# hackeeg-shield.net
KiCad netlist of a schematic drawn in EAGLE
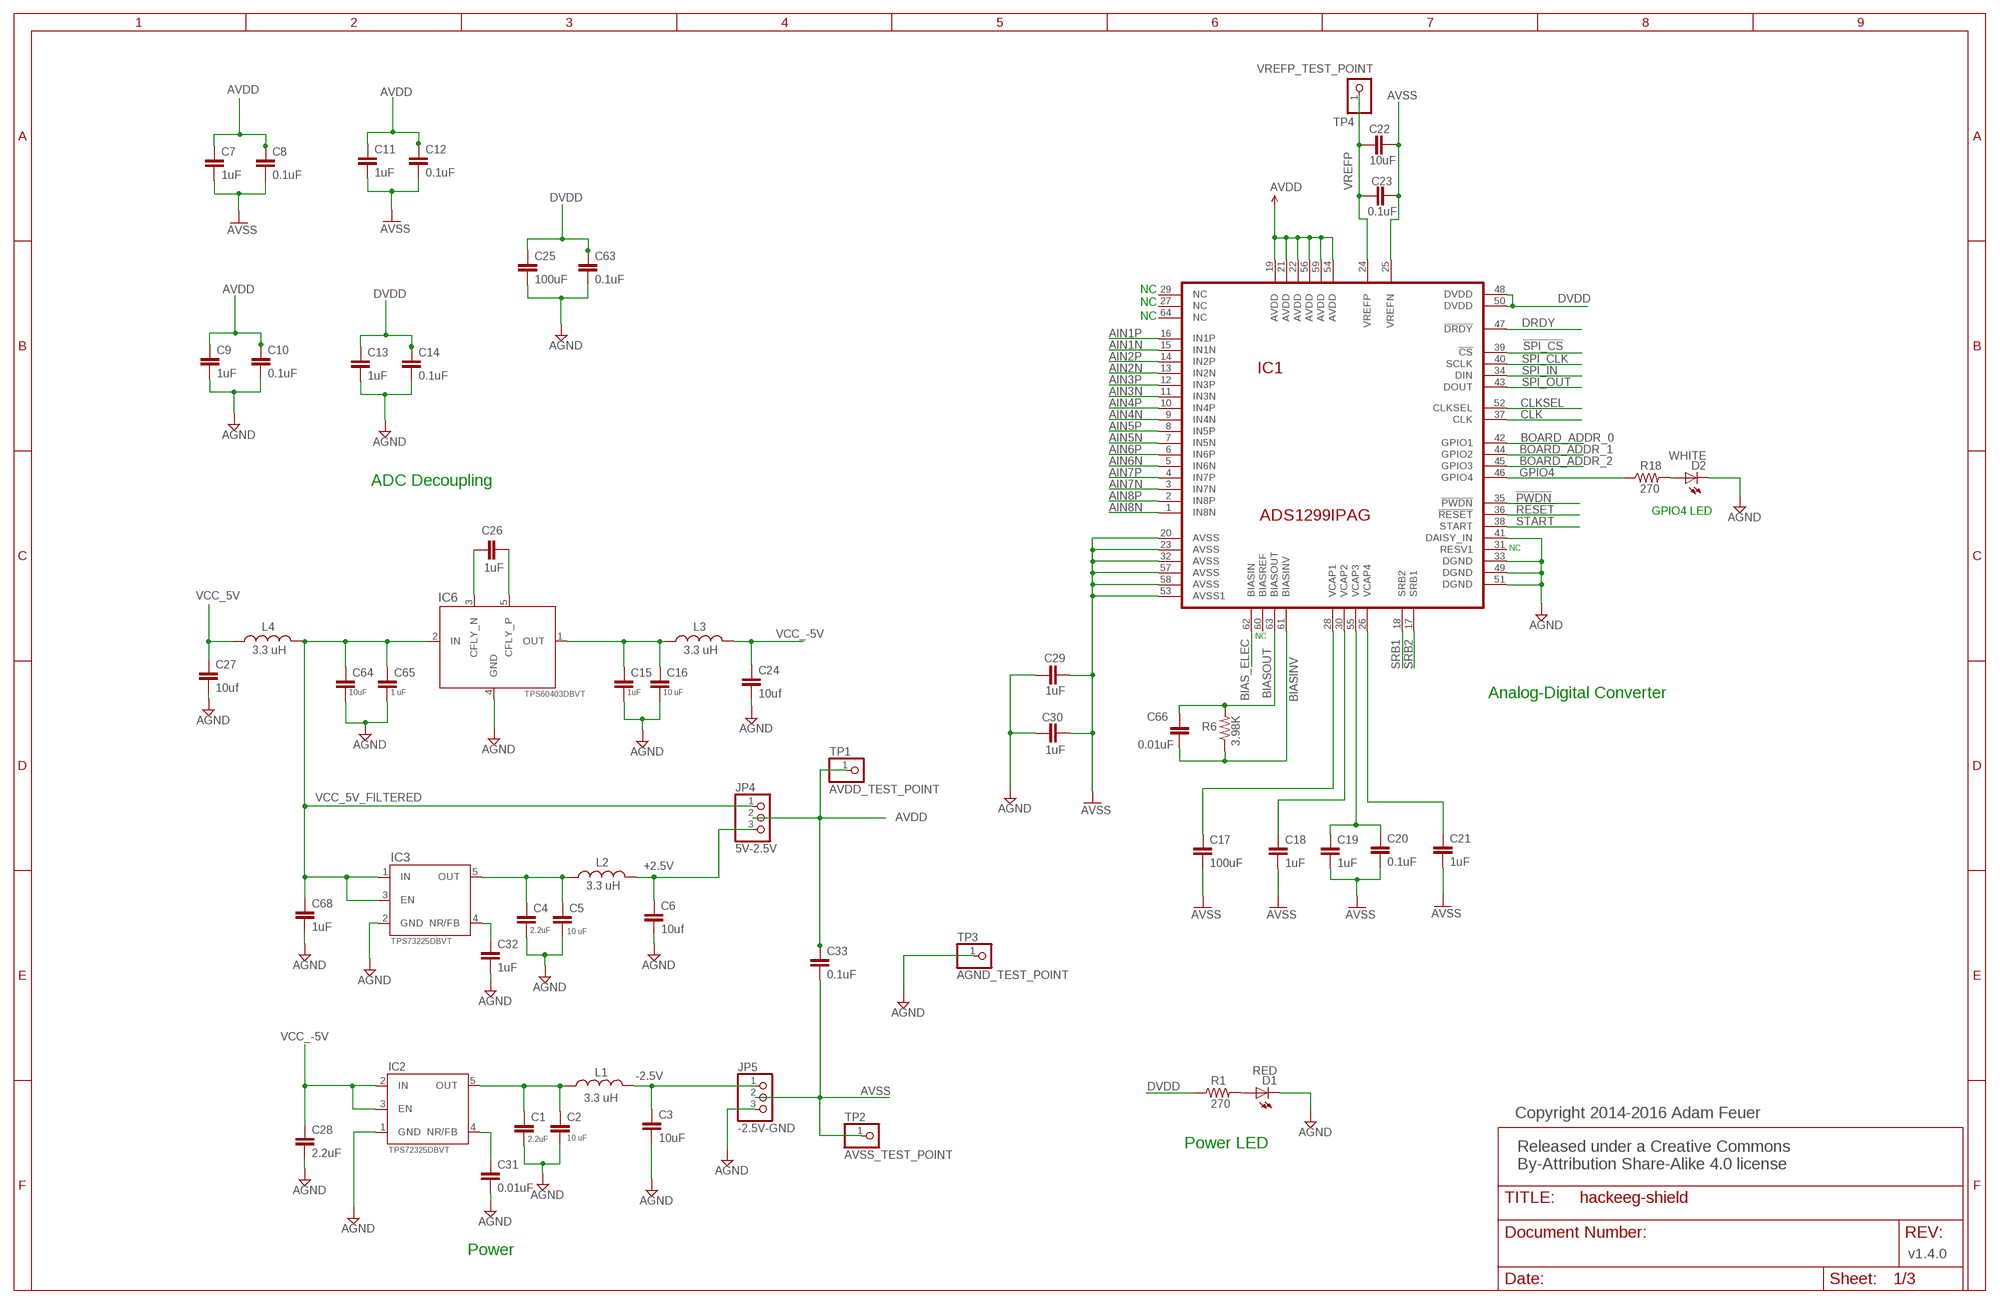
[diagram p0: schematic, sheet 1]
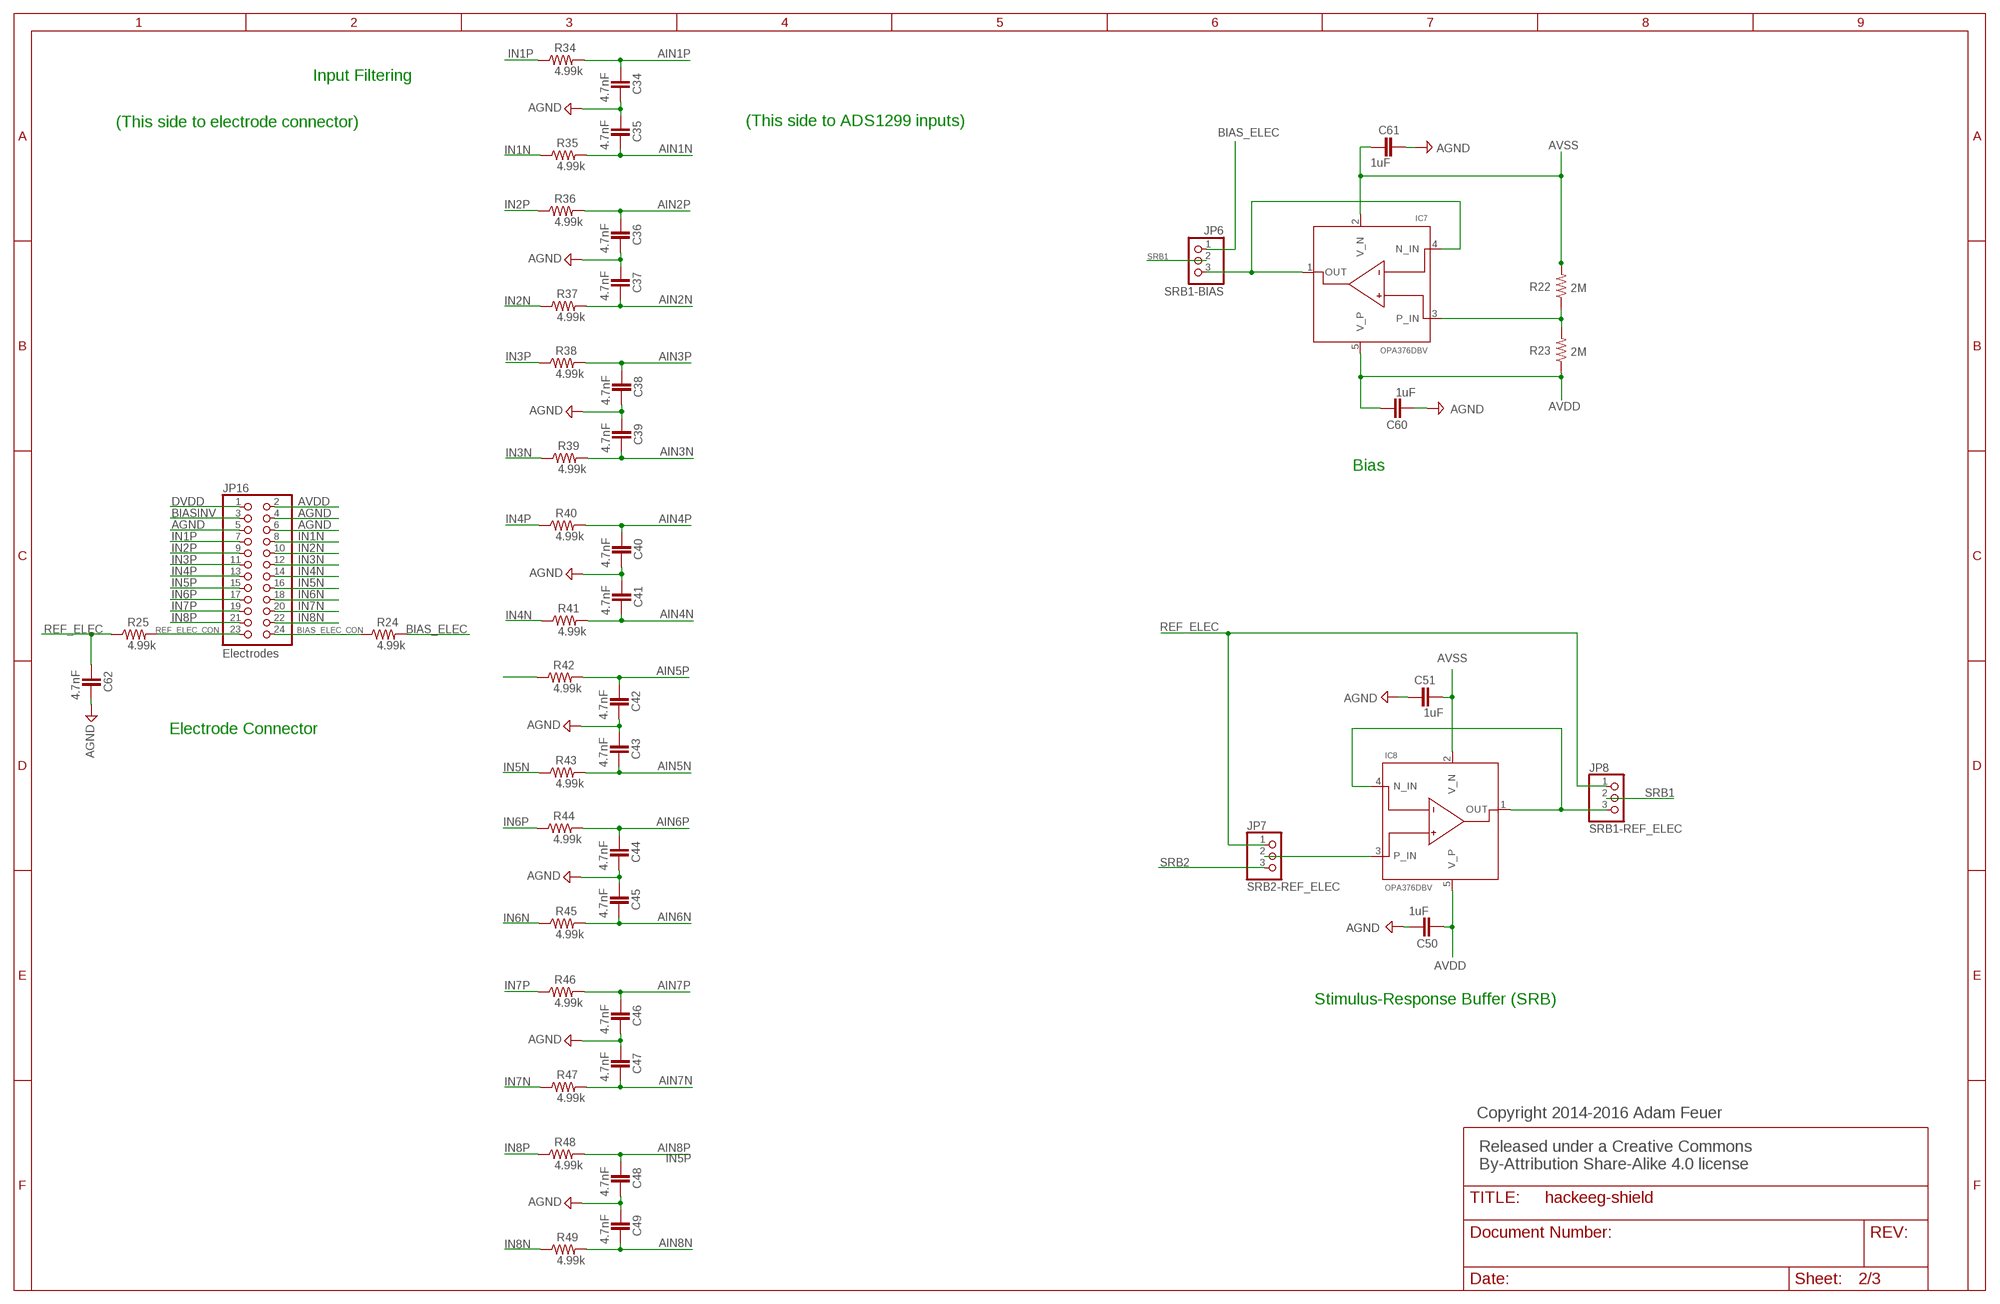
[diagram p1: schematic, sheet 2]
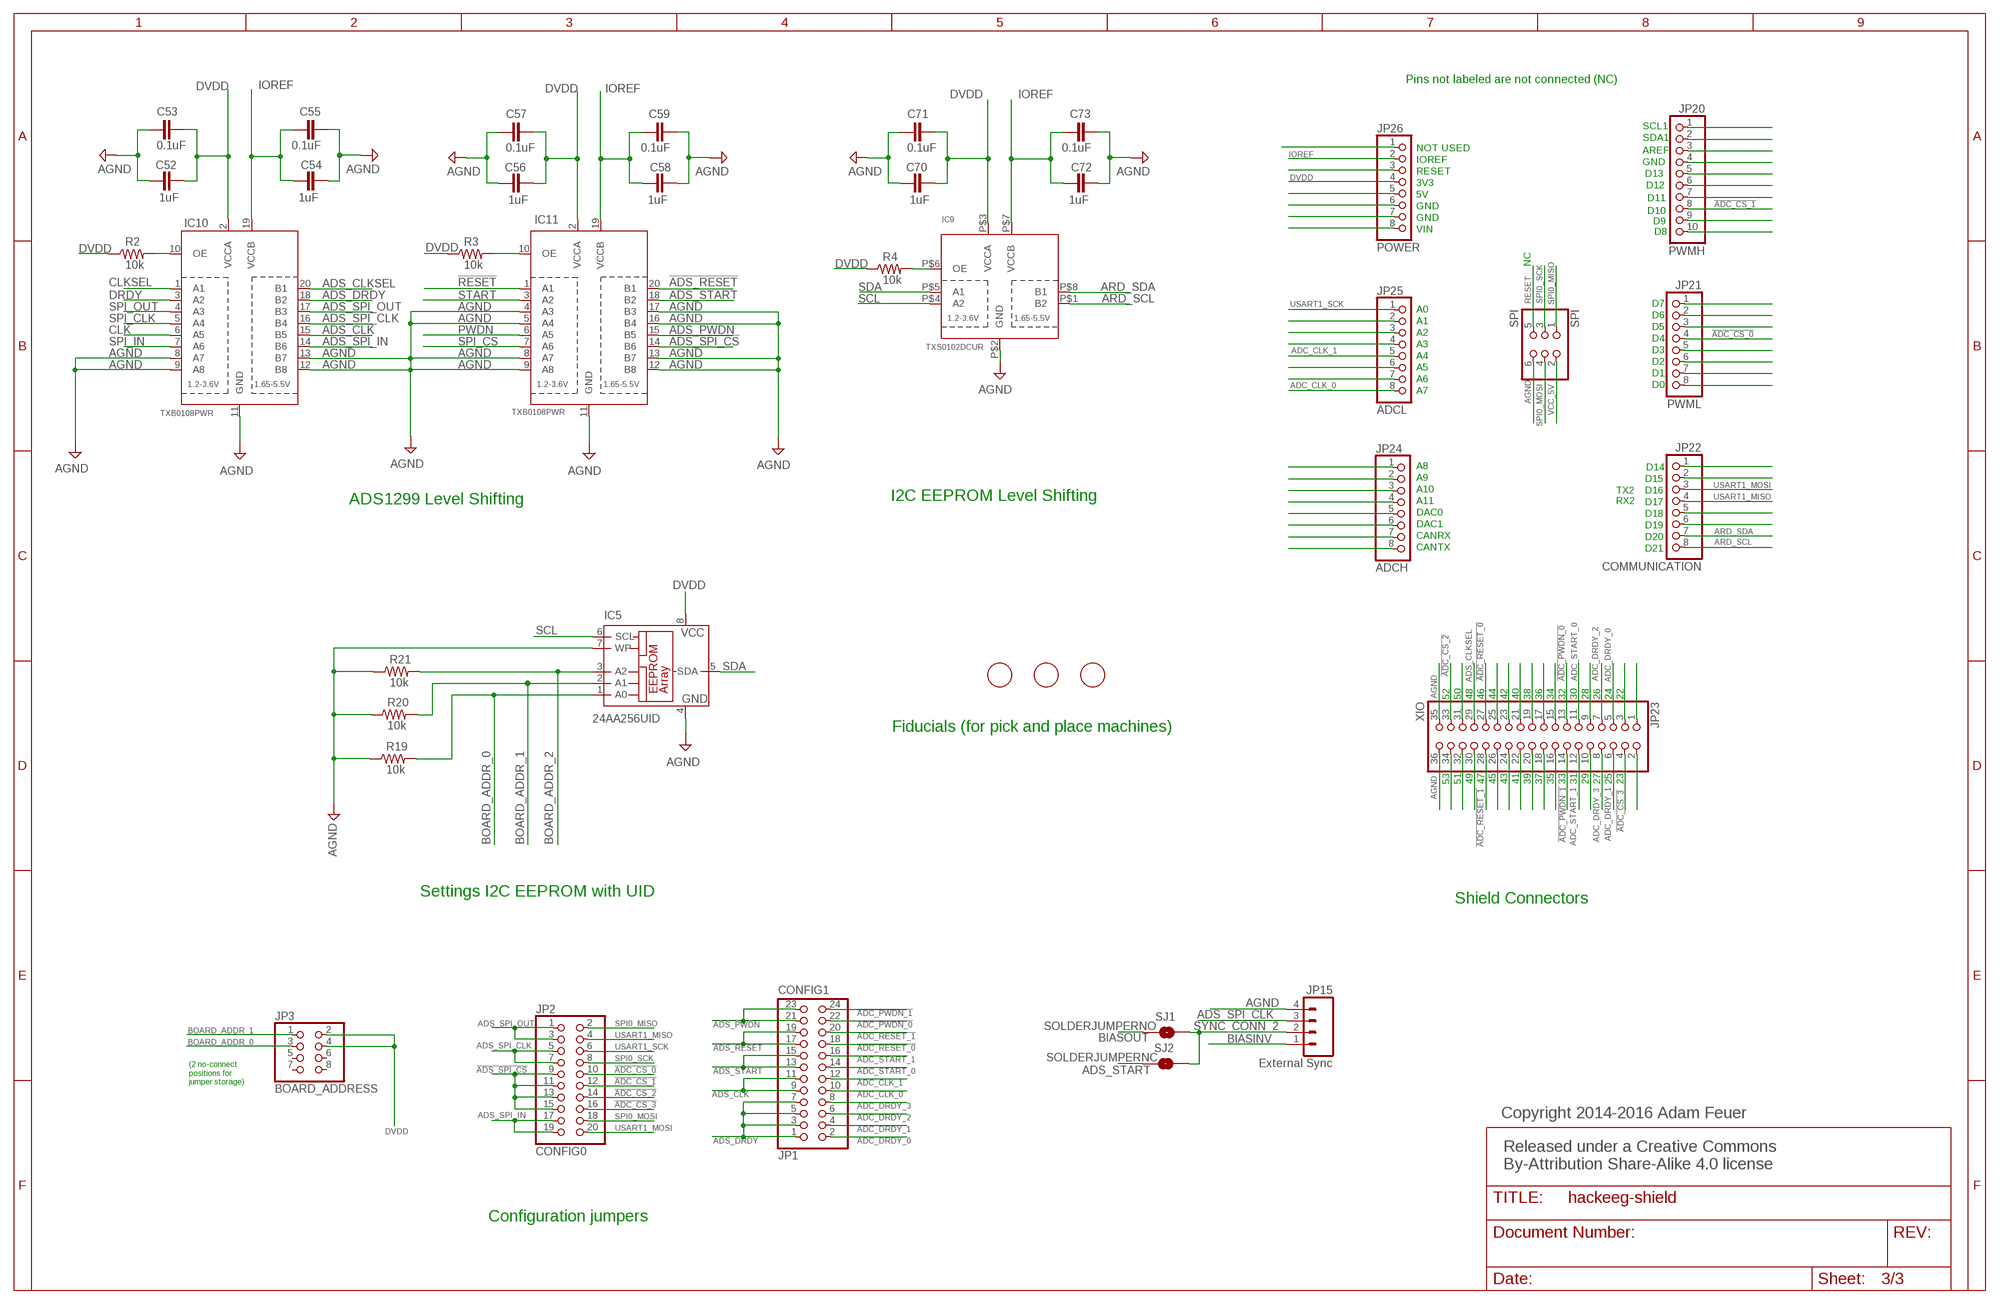
[diagram p2: schematic, sheet 3]

(export (version "E")
  (design (tool "Eeschema 10.0.6"))
  (components
    (comp (ref "C52")
      (value "1uF")
      (footprint "eagle-import:0603-CAP")
      (libsource (lib "eagle-import") (part "CAP0603-CAP"))
    )
    (comp (ref "C53")
      (value "0.1uF")
      (footprint "eagle-import:0603-CAP")
      (libsource (lib "eagle-import") (part "CAP0603-CAP"))
    )
    (comp (ref "C54")
      (value "1uF")
      (footprint "eagle-import:0603-CAP")
      (libsource (lib "eagle-import") (part "CAP0603-CAP"))
    )
    (comp (ref "C55")
      (value "0.1uF")
      (footprint "eagle-import:0603-CAP")
      (libsource (lib "eagle-import") (part "CAP0603-CAP"))
    )
    (comp (ref "C56")
      (value "1uF")
      (footprint "eagle-import:0603-CAP")
      (libsource (lib "eagle-import") (part "CAP0603-CAP"))
    )
    (comp (ref "C57")
      (value "0.1uF")
      (footprint "eagle-import:0603-CAP")
      (libsource (lib "eagle-import") (part "CAP0603-CAP"))
    )
    (comp (ref "C58")
      (value "1uF")
      (footprint "eagle-import:0603-CAP")
      (libsource (lib "eagle-import") (part "CAP0603-CAP"))
    )
    (comp (ref "C59")
      (value "0.1uF")
      (footprint "eagle-import:0603-CAP")
      (libsource (lib "eagle-import") (part "CAP0603-CAP"))
    )
    (comp (ref "C70")
      (value "1uF")
      (footprint "eagle-import:0603-CAP")
      (libsource (lib "eagle-import") (part "CAP0603-CAP"))
    )
    (comp (ref "C71")
      (value "0.1uF")
      (footprint "eagle-import:0603-CAP")
      (libsource (lib "eagle-import") (part "CAP0603-CAP"))
    )
    (comp (ref "C72")
      (value "1uF")
      (footprint "eagle-import:0603-CAP")
      (libsource (lib "eagle-import") (part "CAP0603-CAP"))
    )
    (comp (ref "C73")
      (value "0.1uF")
      (footprint "eagle-import:0603-CAP")
      (libsource (lib "eagle-import") (part "CAP0603-CAP"))
    )
    (comp (ref "IC5")
      (value "24AA256UID")
      (footprint "eagle-import:SO-08")
      (fields (field (name "MF") "MICROCHIP") (field (name "MPN") "24LC256-I/SN"))
      (libsource (lib "eagle-import") (part "24SNLC256"))
    )
    (comp (ref "IC9")
      (value "TXS0102DCUR")
      (footprint "eagle-import:VFSOP-8")
      (libsource (lib "eagle-import") (part "TXS0102"))
    )
    (comp (ref "IC10")
      (value "TXB0108PWR")
      (footprint "eagle-import:TSSOP20")
      (libsource (lib "eagle-import") (part "TXB0108PWR"))
    )
    (comp (ref "IC11")
      (value "TXB0108PWR")
      (footprint "eagle-import:TSSOP20")
      (libsource (lib "eagle-import") (part "TXB0108PWR"))
    )
    (comp (ref "JP1")
      (value "CONFIG1")
      (footprint "eagle-import:2X12")
      (libsource (lib "eagle-import") (part "PINHD-2X12"))
    )
    (comp (ref "JP2")
      (value "CONFIG0")
      (footprint "eagle-import:2X10")
      (libsource (lib "eagle-import") (part "PINHD-2X10"))
    )
    (comp (ref "JP3")
      (value "BOARD_ADDRESS")
      (footprint "eagle-import:2X04")
      (libsource (lib "eagle-import") (part "PINHD-2X4"))
    )
    (comp (ref "JP15")
      (value "External Sync")
      (footprint "eagle-import:JST-4-PTH")
      (libsource (lib "eagle-import") (part "M04JST-PTH"))
    )
    (comp (ref "JP20")
      (value "PWMH")
      (footprint "eagle-import:1X10")
      (libsource (lib "eagle-import") (part "PINHD-1X10"))
    )
    (comp (ref "JP21")
      (value "PWML")
      (footprint "eagle-import:1X08")
      (libsource (lib "eagle-import") (part "PINHD-1X8"))
    )
    (comp (ref "JP22")
      (value "COMMUNICATION")
      (footprint "eagle-import:1X08")
      (libsource (lib "eagle-import") (part "PINHD-1X8"))
    )
    (comp (ref "JP23")
      (value "XIO")
      (footprint "eagle-import:2X18")
      (libsource (lib "eagle-import") (part "PINHD-2X18"))
    )
    (comp (ref "JP24")
      (value "ADCH")
      (footprint "eagle-import:1X08")
      (libsource (lib "eagle-import") (part "PINHD-1X8"))
    )
    (comp (ref "JP25")
      (value "ADCL")
      (footprint "eagle-import:1X08")
      (libsource (lib "eagle-import") (part "PINHD-1X8"))
    )
    (comp (ref "JP26")
      (value "POWER")
      (footprint "eagle-import:1X08")
      (libsource (lib "eagle-import") (part "PINHD-1X8"))
    )
    (comp (ref "R2")
      (value "10k")
      (footprint "eagle-import:0603-RES")
      (libsource (lib "eagle-import") (part "RESISTOR0603-RES"))
    )
    (comp (ref "R3")
      (value "10k")
      (footprint "eagle-import:0603-RES")
      (libsource (lib "eagle-import") (part "RESISTOR0603-RES"))
    )
    (comp (ref "R4")
      (value "10k")
      (footprint "eagle-import:0603-RES")
      (libsource (lib "eagle-import") (part "RESISTOR0603-RES"))
    )
    (comp (ref "R19")
      (value "10k")
      (footprint "eagle-import:0603-RES")
      (libsource (lib "eagle-import") (part "RESISTOR0603-RES"))
    )
    (comp (ref "R20")
      (value "10k")
      (footprint "eagle-import:0603-RES")
      (libsource (lib "eagle-import") (part "RESISTOR0603-RES"))
    )
    (comp (ref "R21")
      (value "10k")
      (footprint "eagle-import:0603-RES")
      (libsource (lib "eagle-import") (part "RESISTOR0603-RES"))
    )
    (comp (ref "SJ1")
      (value "SOLDERJUMPERNO")
      (footprint "eagle-import:SJ_2S-NO")
      (libsource (lib "eagle-import") (part "SOLDERJUMPERNO"))
    )
    (comp (ref "SJ2")
      (value "SOLDERJUMPERNC")
      (footprint "eagle-import:SJ_2S")
      (libsource (lib "eagle-import") (part "SOLDERJUMPERNC"))
    )
    (comp (ref "SPI")
      (value "SPI")
      (footprint "eagle-import:2X03")
      (libsource (lib "eagle-import") (part "PINHD-2X3"))
    )
    (comp (ref "U$2")
      (value "FIDUCIAL")
      (footprint "eagle-import:FIDUCIAL_1MM")
      (libsource (lib "eagle-import") (part "FIDUCIAL"))
    )
    (comp (ref "U$5")
      (value "FIDUCIAL")
      (footprint "eagle-import:FIDUCIAL_1MM")
      (libsource (lib "eagle-import") (part "FIDUCIAL"))
    )
    (comp (ref "U$6")
      (value "FIDUCIAL")
      (footprint "eagle-import:FIDUCIAL_1MM")
      (libsource (lib "eagle-import") (part "FIDUCIAL"))
    )
    (comp (ref "C34")
      (value "4.7nF")
      (footprint "eagle-import:0603-CAP")
      (libsource (lib "eagle-import") (part "CAP0603-CAP"))
    )
    (comp (ref "C35")
      (value "4.7nF")
      (footprint "eagle-import:0603-CAP")
      (libsource (lib "eagle-import") (part "CAP0603-CAP"))
    )
    (comp (ref "C36")
      (value "4.7nF")
      (footprint "eagle-import:0603-CAP")
      (libsource (lib "eagle-import") (part "CAP0603-CAP"))
    )
    (comp (ref "C37")
      (value "4.7nF")
      (footprint "eagle-import:0603-CAP")
      (libsource (lib "eagle-import") (part "CAP0603-CAP"))
    )
    (comp (ref "C38")
      (value "4.7nF")
      (footprint "eagle-import:0603-CAP")
      (libsource (lib "eagle-import") (part "CAP0603-CAP"))
    )
    (comp (ref "C39")
      (value "4.7nF")
      (footprint "eagle-import:0603-CAP")
      (libsource (lib "eagle-import") (part "CAP0603-CAP"))
    )
    (comp (ref "C40")
      (value "4.7nF")
      (footprint "eagle-import:0603-CAP")
      (libsource (lib "eagle-import") (part "CAP0603-CAP"))
    )
    (comp (ref "C41")
      (value "4.7nF")
      (footprint "eagle-import:0603-CAP")
      (libsource (lib "eagle-import") (part "CAP0603-CAP"))
    )
    (comp (ref "C42")
      (value "4.7nF")
      (footprint "eagle-import:0603-CAP")
      (libsource (lib "eagle-import") (part "CAP0603-CAP"))
    )
    (comp (ref "C43")
      (value "4.7nF")
      (footprint "eagle-import:0603-CAP")
      (libsource (lib "eagle-import") (part "CAP0603-CAP"))
    )
    (comp (ref "C44")
      (value "4.7nF")
      (footprint "eagle-import:0603-CAP")
      (libsource (lib "eagle-import") (part "CAP0603-CAP"))
    )
    (comp (ref "C45")
      (value "4.7nF")
      (footprint "eagle-import:0603-CAP")
      (libsource (lib "eagle-import") (part "CAP0603-CAP"))
    )
    (comp (ref "C46")
      (value "4.7nF")
      (footprint "eagle-import:0603-CAP")
      (libsource (lib "eagle-import") (part "CAP0603-CAP"))
    )
    (comp (ref "C47")
      (value "4.7nF")
      (footprint "eagle-import:0603-CAP")
      (libsource (lib "eagle-import") (part "CAP0603-CAP"))
    )
    (comp (ref "C48")
      (value "4.7nF")
      (footprint "eagle-import:0603-CAP")
      (libsource (lib "eagle-import") (part "CAP0603-CAP"))
    )
    (comp (ref "C49")
      (value "4.7nF")
      (footprint "eagle-import:0603-CAP")
      (libsource (lib "eagle-import") (part "CAP0603-CAP"))
    )
    (comp (ref "C50")
      (value "1uF")
      (footprint "eagle-import:0603-CAP")
      (libsource (lib "eagle-import") (part "CAP0603-CAP"))
    )
    (comp (ref "C51")
      (value "1uF")
      (footprint "eagle-import:0603-CAP")
      (libsource (lib "eagle-import") (part "CAP0603-CAP"))
    )
    (comp (ref "C60")
      (value "1uF")
      (footprint "eagle-import:0603-CAP")
      (libsource (lib "eagle-import") (part "CAP0603-CAP"))
    )
    (comp (ref "C61")
      (value "1uF")
      (footprint "eagle-import:0603-CAP")
      (libsource (lib "eagle-import") (part "CAP0603-CAP"))
    )
    (comp (ref "C62")
      (value "4.7nF")
      (footprint "eagle-import:0603-CAP")
      (libsource (lib "eagle-import") (part "CAP0603-CAP"))
    )
    (comp (ref "IC7")
      (value "OPA376DBV")
      (footprint "eagle-import:SOT23-5")
      (libsource (lib "eagle-import") (part "OPA376DBV"))
    )
    (comp (ref "IC8")
      (value "OPA376DBV")
      (footprint "eagle-import:SOT23-5")
      (libsource (lib "eagle-import") (part "OPA376DBV"))
    )
    (comp (ref "JP6")
      (value "SRB1-BIAS")
      (footprint "eagle-import:1X03")
      (libsource (lib "eagle-import") (part "PINHD-1X3"))
    )
    (comp (ref "JP7")
      (value "SRB2-REF_ELEC")
      (footprint "eagle-import:1X03")
      (libsource (lib "eagle-import") (part "PINHD-1X3"))
    )
    (comp (ref "JP8")
      (value "SRB1-REF_ELEC")
      (footprint "eagle-import:1X03")
      (libsource (lib "eagle-import") (part "PINHD-1X3"))
    )
    (comp (ref "JP16")
      (value "Electrodes")
      (footprint "eagle-import:2X12")
      (libsource (lib "eagle-import") (part "PINHD-2X12"))
    )
    (comp (ref "R22")
      (value "2M")
      (footprint "eagle-import:0603-RES")
      (libsource (lib "eagle-import") (part "RESISTOR0603-RES"))
    )
    (comp (ref "R23")
      (value "2M")
      (footprint "eagle-import:0603-RES")
      (libsource (lib "eagle-import") (part "RESISTOR0603-RES"))
    )
    (comp (ref "R24")
      (value "4.99k")
      (footprint "eagle-import:0603-RES")
      (libsource (lib "eagle-import") (part "RESISTOR0603-RES"))
    )
    (comp (ref "R25")
      (value "4.99k")
      (footprint "eagle-import:0603-RES")
      (libsource (lib "eagle-import") (part "RESISTOR0603-RES"))
    )
    (comp (ref "R34")
      (value "4.99k")
      (footprint "eagle-import:0603-RES")
      (libsource (lib "eagle-import") (part "RESISTOR0603-RES"))
    )
    (comp (ref "R35")
      (value "4.99k")
      (footprint "eagle-import:0603-RES")
      (libsource (lib "eagle-import") (part "RESISTOR0603-RES"))
    )
    (comp (ref "R36")
      (value "4.99k")
      (footprint "eagle-import:0603-RES")
      (libsource (lib "eagle-import") (part "RESISTOR0603-RES"))
    )
    (comp (ref "R37")
      (value "4.99k")
      (footprint "eagle-import:0603-RES")
      (libsource (lib "eagle-import") (part "RESISTOR0603-RES"))
    )
    (comp (ref "R38")
      (value "4.99k")
      (footprint "eagle-import:0603-RES")
      (libsource (lib "eagle-import") (part "RESISTOR0603-RES"))
    )
    (comp (ref "R39")
      (value "4.99k")
      (footprint "eagle-import:0603-RES")
      (libsource (lib "eagle-import") (part "RESISTOR0603-RES"))
    )
    (comp (ref "R40")
      (value "4.99k")
      (footprint "eagle-import:0603-RES")
      (libsource (lib "eagle-import") (part "RESISTOR0603-RES"))
    )
    (comp (ref "R41")
      (value "4.99k")
      (footprint "eagle-import:0603-RES")
      (libsource (lib "eagle-import") (part "RESISTOR0603-RES"))
    )
    (comp (ref "R42")
      (value "4.99k")
      (footprint "eagle-import:0603-RES")
      (libsource (lib "eagle-import") (part "RESISTOR0603-RES"))
    )
    (comp (ref "R43")
      (value "4.99k")
      (footprint "eagle-import:0603-RES")
      (libsource (lib "eagle-import") (part "RESISTOR0603-RES"))
    )
    (comp (ref "R44")
      (value "4.99k")
      (footprint "eagle-import:0603-RES")
      (libsource (lib "eagle-import") (part "RESISTOR0603-RES"))
    )
    (comp (ref "R45")
      (value "4.99k")
      (footprint "eagle-import:0603-RES")
      (libsource (lib "eagle-import") (part "RESISTOR0603-RES"))
    )
    (comp (ref "R46")
      (value "4.99k")
      (footprint "eagle-import:0603-RES")
      (libsource (lib "eagle-import") (part "RESISTOR0603-RES"))
    )
    (comp (ref "R47")
      (value "4.99k")
      (footprint "eagle-import:0603-RES")
      (libsource (lib "eagle-import") (part "RESISTOR0603-RES"))
    )
    (comp (ref "R48")
      (value "4.99k")
      (footprint "eagle-import:0603-RES")
      (libsource (lib "eagle-import") (part "RESISTOR0603-RES"))
    )
    (comp (ref "R49")
      (value "4.99k")
      (footprint "eagle-import:0603-RES")
      (libsource (lib "eagle-import") (part "RESISTOR0603-RES"))
    )
    (comp (ref "C1")
      (value "2.2uF")
      (footprint "eagle-import:0603-CAP")
      (libsource (lib "eagle-import") (part "CAP0603-CAP"))
    )
    (comp (ref "C2")
      (value "10 uF")
      (footprint "eagle-import:0603-CAP")
      (libsource (lib "eagle-import") (part "CAP0603-CAP"))
    )
    (comp (ref "C3")
      (value "10uF")
      (footprint "eagle-import:0603-CAP")
      (libsource (lib "eagle-import") (part "CAP0603-CAP"))
    )
    (comp (ref "C4")
      (value "2.2uF")
      (footprint "eagle-import:0603-CAP")
      (libsource (lib "eagle-import") (part "CAP0603-CAP"))
    )
    (comp (ref "C5")
      (value "10 uF")
      (footprint "eagle-import:0603-CAP")
      (libsource (lib "eagle-import") (part "CAP0603-CAP"))
    )
    (comp (ref "C6")
      (value "10uf")
      (footprint "eagle-import:0603-CAP")
      (libsource (lib "eagle-import") (part "CAP0603-CAP"))
    )
    (comp (ref "C7")
      (value "1uF")
      (footprint "eagle-import:0603-CAP")
      (libsource (lib "eagle-import") (part "CAP0603-CAP"))
    )
    (comp (ref "C8")
      (value "0.1uF")
      (footprint "eagle-import:0603-CAP")
      (libsource (lib "eagle-import") (part "CAP0603-CAP"))
    )
    (comp (ref "C9")
      (value "1uF")
      (footprint "eagle-import:0603-CAP")
      (libsource (lib "eagle-import") (part "CAP0603-CAP"))
    )
    (comp (ref "C10")
      (value "0.1uF")
      (footprint "eagle-import:0603-CAP")
      (libsource (lib "eagle-import") (part "CAP0603-CAP"))
    )
    (comp (ref "C11")
      (value "1uF")
      (footprint "eagle-import:0603-CAP")
      (libsource (lib "eagle-import") (part "CAP0603-CAP"))
    )
    (comp (ref "C12")
      (value "0.1uF")
      (footprint "eagle-import:0603-CAP")
      (libsource (lib "eagle-import") (part "CAP0603-CAP"))
    )
    (comp (ref "C13")
      (value "1uF")
      (footprint "eagle-import:0603-CAP")
      (libsource (lib "eagle-import") (part "CAP0603-CAP"))
    )
    (comp (ref "C14")
      (value "0.1uF")
      (footprint "eagle-import:0603-CAP")
      (libsource (lib "eagle-import") (part "CAP0603-CAP"))
    )
    (comp (ref "C15")
      (value "1uF")
      (footprint "eagle-import:0603-CAP")
      (libsource (lib "eagle-import") (part "CAP0603-CAP"))
    )
    (comp (ref "C16")
      (value "10 uF")
      (footprint "eagle-import:0603-CAP")
      (libsource (lib "eagle-import") (part "CAP0603-CAP"))
    )
    (comp (ref "C17")
      (value "100uF")
      (footprint "eagle-import:1210")
      (libsource (lib "eagle-import") (part "CAP1210"))
    )
    (comp (ref "C18")
      (value "1uF")
      (footprint "eagle-import:0603-CAP")
      (libsource (lib "eagle-import") (part "CAP0603-CAP"))
    )
    (comp (ref "C19")
      (value "1uF")
      (footprint "eagle-import:0603-CAP")
      (libsource (lib "eagle-import") (part "CAP0603-CAP"))
    )
    (comp (ref "C20")
      (value "0.1uF")
      (footprint "eagle-import:0603-CAP")
      (libsource (lib "eagle-import") (part "CAP0603-CAP"))
    )
    (comp (ref "C21")
      (value "1uF")
      (footprint "eagle-import:0603-CAP")
      (libsource (lib "eagle-import") (part "CAP0603-CAP"))
    )
    (comp (ref "C22")
      (value "10uF")
      (footprint "eagle-import:0603-CAP")
      (libsource (lib "eagle-import") (part "CAP0603-CAP"))
    )
    (comp (ref "C23")
      (value "0.1uF")
      (footprint "eagle-import:0603-CAP")
      (libsource (lib "eagle-import") (part "CAP0603-CAP"))
    )
    (comp (ref "C24")
      (value "10uf")
      (footprint "eagle-import:0603-CAP")
      (libsource (lib "eagle-import") (part "CAP0603-CAP"))
    )
    (comp (ref "C25")
      (value "100uF")
      (footprint "eagle-import:1210")
      (libsource (lib "eagle-import") (part "CAP1210"))
    )
    (comp (ref "C26")
      (value "1uF")
      (footprint "eagle-import:0603-CAP")
      (libsource (lib "eagle-import") (part "CAP0603-CAP"))
    )
    (comp (ref "C27")
      (value "10uf")
      (footprint "eagle-import:0603-CAP")
      (libsource (lib "eagle-import") (part "CAP0603-CAP"))
    )
    (comp (ref "C28")
      (value "2.2uF")
      (footprint "eagle-import:0603-CAP")
      (libsource (lib "eagle-import") (part "CAP0603-CAP"))
    )
    (comp (ref "C29")
      (value "1uF")
      (footprint "eagle-import:0603-CAP")
      (libsource (lib "eagle-import") (part "CAP0603-CAP"))
    )
    (comp (ref "C30")
      (value "1uF")
      (footprint "eagle-import:0603-CAP")
      (libsource (lib "eagle-import") (part "CAP0603-CAP"))
    )
    (comp (ref "C31")
      (value "0.01uF")
      (footprint "eagle-import:0603-CAP")
      (libsource (lib "eagle-import") (part "CAP0603-CAP"))
    )
    (comp (ref "C32")
      (value "1uF")
      (footprint "eagle-import:0603-CAP")
      (libsource (lib "eagle-import") (part "CAP0603-CAP"))
    )
    (comp (ref "C33")
      (value "0.1uF")
      (footprint "eagle-import:0603-CAP")
      (libsource (lib "eagle-import") (part "CAP0603-CAP"))
    )
    (comp (ref "C63")
      (value "0.1uF")
      (footprint "eagle-import:0603-CAP")
      (libsource (lib "eagle-import") (part "CAP0603-CAP"))
    )
    (comp (ref "C64")
      (value "10uF")
      (footprint "eagle-import:0603-CAP")
      (libsource (lib "eagle-import") (part "CAP0603-CAP"))
    )
    (comp (ref "C65")
      (value "1 uF")
      (footprint "eagle-import:0603-CAP")
      (libsource (lib "eagle-import") (part "CAP0603-CAP"))
    )
    (comp (ref "C66")
      (value "0.01uF")
      (footprint "eagle-import:0603-CAP")
      (libsource (lib "eagle-import") (part "CAP0603-CAP"))
    )
    (comp (ref "C68")
      (value "1uF")
      (footprint "eagle-import:0603-CAP")
      (libsource (lib "eagle-import") (part "CAP0603-CAP"))
    )
    (comp (ref "D1")
      (value "RED")
      (footprint "eagle-import:LED-1206")
      (libsource (lib "eagle-import") (part "LED-RED1206"))
    )
    (comp (ref "D2")
      (value "WHITE")
      (footprint "eagle-import:LED-1206")
      (libsource (lib "eagle-import") (part "LED-WHITE"))
    )
    (comp (ref "IC1")
      (value "ADS1299IPAG")
      (footprint "eagle-import:TQFP64")
      (libsource (lib "eagle-import") (part "ADS1299PAG"))
    )
    (comp (ref "IC2")
      (value "TPS72325DBVT")
      (footprint "eagle-import:SOT23-5")
      (libsource (lib "eagle-import") (part "TPS723xx_TPS732XXDBV"))
    )
    (comp (ref "IC3")
      (value "TPS73225DBVT")
      (footprint "eagle-import:SOT23-5")
      (libsource (lib "eagle-import") (part "TPS732XXDBV"))
    )
    (comp (ref "IC6")
      (value "TPS60403DBVT")
      (footprint "eagle-import:SOT23-5")
      (libsource (lib "eagle-import") (part "TPS604XXDBV"))
    )
    (comp (ref "JP4")
      (value "5V-2.5V")
      (footprint "eagle-import:1X03")
      (libsource (lib "eagle-import") (part "headers_PINHD-1X3"))
    )
    (comp (ref "JP5")
      (value "-2.5V-GND")
      (footprint "eagle-import:1X03")
      (libsource (lib "eagle-import") (part "headers_PINHD-1X3"))
    )
    (comp (ref "L1")
      (value "3.3 uH")
      (footprint "eagle-import:0805")
      (libsource (lib "eagle-import") (part "INDUCTOR0805"))
    )
    (comp (ref "L2")
      (value "3.3 uH")
      (footprint "eagle-import:0805")
      (libsource (lib "eagle-import") (part "INDUCTOR0805"))
    )
    (comp (ref "L3")
      (value "3.3 uH")
      (footprint "eagle-import:0805")
      (libsource (lib "eagle-import") (part "INDUCTOR0805"))
    )
    (comp (ref "L4")
      (value "3.3 uH")
      (footprint "eagle-import:0805")
      (libsource (lib "eagle-import") (part "INDUCTOR0805"))
    )
    (comp (ref "R1")
      (value "270")
      (footprint "eagle-import:0603-RES")
      (libsource (lib "eagle-import") (part "RESISTOR0603-RES"))
    )
    (comp (ref "R6")
      (value "3.98K")
      (footprint "eagle-import:0603-RES")
      (libsource (lib "eagle-import") (part "RESISTOR0603-RES"))
    )
    (comp (ref "R18")
      (value "270")
      (footprint "eagle-import:0603-RES")
      (libsource (lib "eagle-import") (part "RESISTOR0603-RES"))
    )
    (comp (ref "TP1")
      (value "AVDD_TEST_POINT")
      (footprint "eagle-import:1X01")
      (libsource (lib "eagle-import") (part "PINHD-1X1"))
    )
    (comp (ref "TP2")
      (value "AVSS_TEST_POINT")
      (footprint "eagle-import:1X01")
      (libsource (lib "eagle-import") (part "PINHD-1X1"))
    )
    (comp (ref "TP3")
      (value "AGND_TEST_POINT")
      (footprint "eagle-import:1X01")
      (libsource (lib "eagle-import") (part "PINHD-1X1"))
    )
    (comp (ref "TP4")
      (value "VREFP_TEST_POINT")
      (footprint "eagle-import:1X01")
      (libsource (lib "eagle-import") (part "PINHD-1X1"))
    )
  )
  (nets
    (net (code "1") (name "+2.5V") (class "Default")
      (node (ref "C6") (pin "1") (pinfunction "1_1") (pintype "passive"))
      (node (ref "JP4") (pin "3") (pinfunction "3_3") (pintype "passive"))
      (node (ref "L2") (pin "2") (pinfunction "2_2") (pintype "passive"))
    )
    (net (code "2") (name "-2.5V") (class "Default")
      (node (ref "C3") (pin "1") (pinfunction "1_1") (pintype "passive"))
      (node (ref "JP5") (pin "1") (pinfunction "1_1") (pintype "passive"))
      (node (ref "L1") (pin "2") (pinfunction "2_2") (pintype "passive"))
    )
    (net (code "3") (name "ADC_CLK_0") (class "Default")
      (node (ref "JP1") (pin "10") (pinfunction "10_10") (pintype "passive"))
      (node (ref "JP25") (pin "8") (pinfunction "8_8") (pintype "passive"))
    )
    (net (code "4") (name "ADC_CLK_1") (class "Default")
      (node (ref "JP1") (pin "12") (pinfunction "12_12") (pintype "passive"))
      (node (ref "JP25") (pin "5") (pinfunction "5_5") (pintype "passive"))
    )
    (net (code "5") (name "ADC_DRDY_0") (class "Default")
      (node (ref "JP1") (pin "2") (pinfunction "2_2") (pintype "passive"))
      (node (ref "JP23") (pin "5") (pinfunction "5_5") (pintype "passive"))
    )
    (net (code "6") (name "ADC_DRDY_1") (class "Default")
      (node (ref "JP1") (pin "4") (pinfunction "4_4") (pintype "passive"))
      (node (ref "JP23") (pin "6") (pinfunction "6_6") (pintype "passive"))
    )
    (net (code "7") (name "ADC_DRDY_2") (class "Default")
      (node (ref "JP1") (pin "6") (pinfunction "6_6") (pintype "passive"))
      (node (ref "JP23") (pin "7") (pinfunction "7_7") (pintype "passive"))
    )
    (net (code "8") (name "ADC_DRDY_3") (class "Default")
      (node (ref "JP1") (pin "8") (pinfunction "8_8") (pintype "passive"))
      (node (ref "JP23") (pin "8") (pinfunction "8_8") (pintype "passive"))
    )
    (net (code "9") (name "ADC_START_0") (class "Default")
      (node (ref "JP1") (pin "14") (pinfunction "14_14") (pintype "passive"))
      (node (ref "JP23") (pin "11") (pinfunction "11_11") (pintype "passive"))
    )
    (net (code "10") (name "ADC_START_1") (class "Default")
      (node (ref "JP1") (pin "16") (pinfunction "16_16") (pintype "passive"))
      (node (ref "JP23") (pin "12") (pinfunction "12_12") (pintype "passive"))
    )
    (net (code "11") (name "ADS_CLK") (class "Default")
      (node (ref "IC10") (pin "15") (pinfunction "B5_15") (pintype "bidirectional"))
      (node (ref "JP1") (pin "11") (pinfunction "11_11") (pintype "passive"))
      (node (ref "JP1") (pin "9") (pinfunction "9_9") (pintype "passive"))
    )
    (net (code "12") (name "ADS_CLKSEL") (class "Default")
      (node (ref "IC10") (pin "20") (pinfunction "B1_20") (pintype "bidirectional"))
      (node (ref "JP23") (pin "29") (pinfunction "29_29") (pintype "passive"))
    )
    (net (code "13") (name "ADS_DRDY") (class "Default")
      (node (ref "IC10") (pin "18") (pinfunction "B2_18") (pintype "bidirectional"))
      (node (ref "JP1") (pin "1") (pinfunction "1_1") (pintype "passive"))
      (node (ref "JP1") (pin "3") (pinfunction "3_3") (pintype "passive"))
      (node (ref "JP1") (pin "5") (pinfunction "5_5") (pintype "passive"))
      (node (ref "JP1") (pin "7") (pinfunction "7_7") (pintype "passive"))
    )
    (net (code "14") (name "ADS_SPI_CLK") (class "Default")
      (node (ref "IC10") (pin "16") (pinfunction "B4_16") (pintype "bidirectional"))
      (node (ref "JP15") (pin "3") (pinfunction "3_3") (pintype "passive"))
      (node (ref "JP2") (pin "5") (pinfunction "5_5") (pintype "passive"))
      (node (ref "JP2") (pin "7") (pinfunction "7_7") (pintype "passive"))
    )
    (net (code "15") (name "ADS_SPI_IN") (class "Default")
      (node (ref "IC10") (pin "14") (pinfunction "B6_14") (pintype "bidirectional"))
      (node (ref "JP2") (pin "17") (pinfunction "17_17") (pintype "passive"))
      (node (ref "JP2") (pin "19") (pinfunction "19_19") (pintype "passive"))
    )
    (net (code "16") (name "ADS_SPI_OUT") (class "Default")
      (node (ref "IC10") (pin "17") (pinfunction "B3_17") (pintype "bidirectional"))
      (node (ref "JP2") (pin "1") (pinfunction "1_1") (pintype "passive"))
      (node (ref "JP2") (pin "3") (pinfunction "3_3") (pintype "passive"))
    )
    (net (code "17") (name "ADS_START") (class "Default")
      (node (ref "IC11") (pin "18") (pinfunction "B2_18") (pintype "bidirectional"))
      (node (ref "JP1") (pin "13") (pinfunction "13_13") (pintype "passive"))
      (node (ref "JP1") (pin "15") (pinfunction "15_15") (pintype "passive"))
      (node (ref "SJ2") (pin "1") (pinfunction "1_1") (pintype "passive"))
    )
    (net (code "18") (name "AGND") (class "Default")
      (node (ref "C1") (pin "2") (pinfunction "2_2") (pintype "passive"))
      (node (ref "C10") (pin "2") (pinfunction "2_2") (pintype "passive"))
      (node (ref "C13") (pin "2") (pinfunction "2_2") (pintype "passive"))
      (node (ref "C14") (pin "2") (pinfunction "2_2") (pintype "passive"))
      (node (ref "C15") (pin "2") (pinfunction "2_2") (pintype "passive"))
      (node (ref "C16") (pin "2") (pinfunction "2_2") (pintype "passive"))
      (node (ref "C2") (pin "2") (pinfunction "2_2") (pintype "passive"))
      (node (ref "C24") (pin "2") (pinfunction "2_2") (pintype "passive"))
      (node (ref "C25") (pin "2") (pinfunction "2_2") (pintype "passive"))
      (node (ref "C27") (pin "2") (pinfunction "2_2") (pintype "passive"))
      (node (ref "C28") (pin "2") (pinfunction "2_2") (pintype "passive"))
      (node (ref "C29") (pin "1") (pinfunction "1_1") (pintype "passive"))
      (node (ref "C3") (pin "2") (pinfunction "2_2") (pintype "passive"))
      (node (ref "C30") (pin "1") (pinfunction "1_1") (pintype "passive"))
      (node (ref "C31") (pin "2") (pinfunction "2_2") (pintype "passive"))
      (node (ref "C32") (pin "2") (pinfunction "2_2") (pintype "passive"))
      (node (ref "C34") (pin "2") (pinfunction "2_2") (pintype "passive"))
      (node (ref "C35") (pin "1") (pinfunction "1_1") (pintype "passive"))
      (node (ref "C36") (pin "2") (pinfunction "2_2") (pintype "passive"))
      (node (ref "C37") (pin "1") (pinfunction "1_1") (pintype "passive"))
      (node (ref "C38") (pin "2") (pinfunction "2_2") (pintype "passive"))
      (node (ref "C39") (pin "1") (pinfunction "1_1") (pintype "passive"))
      (node (ref "C4") (pin "2") (pinfunction "2_2") (pintype "passive"))
      (node (ref "C40") (pin "2") (pinfunction "2_2") (pintype "passive"))
      (node (ref "C41") (pin "1") (pinfunction "1_1") (pintype "passive"))
      (node (ref "C42") (pin "2") (pinfunction "2_2") (pintype "passive"))
      (node (ref "C43") (pin "1") (pinfunction "1_1") (pintype "passive"))
      (node (ref "C44") (pin "2") (pinfunction "2_2") (pintype "passive"))
      (node (ref "C45") (pin "1") (pinfunction "1_1") (pintype "passive"))
      (node (ref "C46") (pin "2") (pinfunction "2_2") (pintype "passive"))
      (node (ref "C47") (pin "1") (pinfunction "1_1") (pintype "passive"))
      (node (ref "C48") (pin "2") (pinfunction "2_2") (pintype "passive"))
      (node (ref "C49") (pin "1") (pinfunction "1_1") (pintype "passive"))
      (node (ref "C5") (pin "2") (pinfunction "2_2") (pintype "passive"))
      (node (ref "C50") (pin "2") (pinfunction "2_2") (pintype "passive"))
      (node (ref "C51") (pin "1") (pinfunction "1_1") (pintype "passive"))
      (node (ref "C52") (pin "1") (pinfunction "1_1") (pintype "passive"))
      (node (ref "C53") (pin "1") (pinfunction "1_1") (pintype "passive"))
      (node (ref "C54") (pin "1") (pinfunction "1_1") (pintype "passive"))
      (node (ref "C55") (pin "1") (pinfunction "1_1") (pintype "passive"))
      (node (ref "C56") (pin "1") (pinfunction "1_1") (pintype "passive"))
      (node (ref "C57") (pin "1") (pinfunction "1_1") (pintype "passive"))
      (node (ref "C58") (pin "1") (pinfunction "1_1") (pintype "passive"))
      (node (ref "C59") (pin "1") (pinfunction "1_1") (pintype "passive"))
      (node (ref "C6") (pin "2") (pinfunction "2_2") (pintype "passive"))
      (node (ref "C60") (pin "2") (pinfunction "2_2") (pintype "passive"))
      (node (ref "C61") (pin "1") (pinfunction "1_1") (pintype "passive"))
      (node (ref "C62") (pin "2") (pinfunction "2_2") (pintype "passive"))
      (node (ref "C63") (pin "2") (pinfunction "2_2") (pintype "passive"))
      (node (ref "C64") (pin "2") (pinfunction "2_2") (pintype "passive"))
      (node (ref "C65") (pin "2") (pinfunction "2_2") (pintype "passive"))
      (node (ref "C68") (pin "2") (pinfunction "2_2") (pintype "passive"))
      (node (ref "C70") (pin "1") (pinfunction "1_1") (pintype "passive"))
      (node (ref "C71") (pin "1") (pinfunction "1_1") (pintype "passive"))
      (node (ref "C72") (pin "1") (pinfunction "1_1") (pintype "passive"))
      (node (ref "C73") (pin "1") (pinfunction "1_1") (pintype "passive"))
      (node (ref "C9") (pin "2") (pinfunction "2_2") (pintype "passive"))
      (node (ref "D1") (pin "C") (pinfunction "C_C") (pintype "passive"))
      (node (ref "D2") (pin "C") (pinfunction "C_C") (pintype "passive"))
      (node (ref "IC1") (pin "33") (pinfunction "DGND_33") (pintype "power_in"))
      (node (ref "IC1") (pin "41") (pinfunction "DAISY_IN_41") (pintype "input"))
      (node (ref "IC1") (pin "49") (pinfunction "DGND_49") (pintype "power_in"))
      (node (ref "IC1") (pin "51") (pinfunction "DGND_51") (pintype "power_in"))
      (node (ref "IC10") (pin "11") (pinfunction "GND_11") (pintype "bidirectional"))
      (node (ref "IC10") (pin "12") (pinfunction "B8_12") (pintype "bidirectional"))
      (node (ref "IC10") (pin "13") (pinfunction "B7_13") (pintype "bidirectional"))
      (node (ref "IC10") (pin "8") (pinfunction "A7_8") (pintype "bidirectional"))
      (node (ref "IC10") (pin "9") (pinfunction "A8_9") (pintype "bidirectional"))
      (node (ref "IC11") (pin "11") (pinfunction "GND_11") (pintype "bidirectional"))
      (node (ref "IC11") (pin "12") (pinfunction "B8_12") (pintype "bidirectional"))
      (node (ref "IC11") (pin "13") (pinfunction "B7_13") (pintype "bidirectional"))
      (node (ref "IC11") (pin "16") (pinfunction "B4_16") (pintype "bidirectional"))
      (node (ref "IC11") (pin "17") (pinfunction "B3_17") (pintype "bidirectional"))
      (node (ref "IC11") (pin "4") (pinfunction "A3_4") (pintype "bidirectional"))
      (node (ref "IC11") (pin "5") (pinfunction "A4_5") (pintype "bidirectional"))
      (node (ref "IC11") (pin "8") (pinfunction "A7_8") (pintype "bidirectional"))
      (node (ref "IC11") (pin "9") (pinfunction "A8_9") (pintype "bidirectional"))
      (node (ref "IC2") (pin "1") (pinfunction "GND_1") (pintype "bidirectional"))
      (node (ref "IC3") (pin "2") (pinfunction "GND_2") (pintype "bidirectional"))
      (node (ref "IC5") (pin "4") (pinfunction "GND_4") (pintype "power_in"))
      (node (ref "IC5") (pin "7") (pinfunction "WP_7") (pintype "input"))
      (node (ref "IC6") (pin "4") (pinfunction "GND_4") (pintype "bidirectional"))
      (node (ref "IC9") (pin "P$2") (pinfunction "GND_P$2") (pintype "bidirectional"))
      (node (ref "JP15") (pin "4") (pinfunction "4_4") (pintype "passive"))
      (node (ref "JP16") (pin "4") (pinfunction "4_4") (pintype "passive"))
      (node (ref "JP16") (pin "5") (pinfunction "5_5") (pintype "passive"))
      (node (ref "JP16") (pin "6") (pinfunction "6_6") (pintype "passive"))
      (node (ref "JP23") (pin "35") (pinfunction "35_35") (pintype "passive"))
      (node (ref "JP23") (pin "36") (pinfunction "36_36") (pintype "passive"))
      (node (ref "JP5") (pin "3") (pinfunction "3_3") (pintype "passive"))
      (node (ref "R19") (pin "1") (pinfunction "1_1") (pintype "passive"))
      (node (ref "R20") (pin "1") (pinfunction "1_1") (pintype "passive"))
      (node (ref "R21") (pin "1") (pinfunction "1_1") (pintype "passive"))
      (node (ref "SPI") (pin "6") (pinfunction "6_6") (pintype "passive"))
      (node (ref "TP3") (pin "1") (pinfunction "1_1") (pintype "passive"))
    )
    (net (code "19") (name "AIN1N") (class "Default")
      (node (ref "C35") (pin "2") (pinfunction "2_2") (pintype "passive"))
      (node (ref "IC1") (pin "15") (pinfunction "IN1N_15") (pintype "input"))
      (node (ref "R35") (pin "2") (pinfunction "2_2") (pintype "passive"))
    )
    (net (code "20") (name "AIN1P") (class "Default")
      (node (ref "C34") (pin "1") (pinfunction "1_1") (pintype "passive"))
      (node (ref "IC1") (pin "16") (pinfunction "IN1P_16") (pintype "input"))
      (node (ref "R34") (pin "2") (pinfunction "2_2") (pintype "passive"))
    )
    (net (code "21") (name "AIN2N") (class "Default")
      (node (ref "C37") (pin "2") (pinfunction "2_2") (pintype "passive"))
      (node (ref "IC1") (pin "13") (pinfunction "IN2N_13") (pintype "input"))
      (node (ref "R37") (pin "2") (pinfunction "2_2") (pintype "passive"))
    )
    (net (code "22") (name "AIN2P") (class "Default")
      (node (ref "C36") (pin "1") (pinfunction "1_1") (pintype "passive"))
      (node (ref "IC1") (pin "14") (pinfunction "IN2P_14") (pintype "input"))
      (node (ref "R36") (pin "2") (pinfunction "2_2") (pintype "passive"))
    )
    (net (code "23") (name "AIN3N") (class "Default")
      (node (ref "C39") (pin "2") (pinfunction "2_2") (pintype "passive"))
      (node (ref "IC1") (pin "11") (pinfunction "IN3N_11") (pintype "input"))
      (node (ref "R39") (pin "2") (pinfunction "2_2") (pintype "passive"))
    )
    (net (code "24") (name "AIN3P") (class "Default")
      (node (ref "C38") (pin "1") (pinfunction "1_1") (pintype "passive"))
      (node (ref "IC1") (pin "12") (pinfunction "IN3P_12") (pintype "input"))
      (node (ref "R38") (pin "2") (pinfunction "2_2") (pintype "passive"))
    )
    (net (code "25") (name "AIN4N") (class "Default")
      (node (ref "C41") (pin "2") (pinfunction "2_2") (pintype "passive"))
      (node (ref "IC1") (pin "9") (pinfunction "IN4N_9") (pintype "input"))
      (node (ref "R41") (pin "2") (pinfunction "2_2") (pintype "passive"))
    )
    (net (code "26") (name "AIN4P") (class "Default")
      (node (ref "C40") (pin "1") (pinfunction "1_1") (pintype "passive"))
      (node (ref "IC1") (pin "10") (pinfunction "IN4P_10") (pintype "input"))
      (node (ref "R40") (pin "2") (pinfunction "2_2") (pintype "passive"))
    )
    (net (code "27") (name "AIN5N") (class "Default")
      (node (ref "C43") (pin "2") (pinfunction "2_2") (pintype "passive"))
      (node (ref "IC1") (pin "7") (pinfunction "IN5N_7") (pintype "input"))
      (node (ref "R43") (pin "2") (pinfunction "2_2") (pintype "passive"))
    )
    (net (code "28") (name "AIN5P") (class "Default")
      (node (ref "C42") (pin "1") (pinfunction "1_1") (pintype "passive"))
      (node (ref "IC1") (pin "8") (pinfunction "IN5P_8") (pintype "input"))
      (node (ref "R42") (pin "2") (pinfunction "2_2") (pintype "passive"))
    )
    (net (code "29") (name "AIN6N") (class "Default")
      (node (ref "C45") (pin "2") (pinfunction "2_2") (pintype "passive"))
      (node (ref "IC1") (pin "5") (pinfunction "IN6N_5") (pintype "input"))
      (node (ref "R45") (pin "2") (pinfunction "2_2") (pintype "passive"))
    )
    (net (code "30") (name "AIN6P") (class "Default")
      (node (ref "C44") (pin "1") (pinfunction "1_1") (pintype "passive"))
      (node (ref "IC1") (pin "6") (pinfunction "IN6P_6") (pintype "input"))
      (node (ref "R44") (pin "2") (pinfunction "2_2") (pintype "passive"))
    )
    (net (code "31") (name "AIN7N") (class "Default")
      (node (ref "C47") (pin "2") (pinfunction "2_2") (pintype "passive"))
      (node (ref "IC1") (pin "3") (pinfunction "IN7N_3") (pintype "input"))
      (node (ref "R47") (pin "2") (pinfunction "2_2") (pintype "passive"))
    )
    (net (code "32") (name "AIN7P") (class "Default")
      (node (ref "C46") (pin "1") (pinfunction "1_1") (pintype "passive"))
      (node (ref "IC1") (pin "4") (pinfunction "IN7P_4") (pintype "input"))
      (node (ref "R46") (pin "2") (pinfunction "2_2") (pintype "passive"))
    )
    (net (code "33") (name "AIN8N") (class "Default")
      (node (ref "C49") (pin "2") (pinfunction "2_2") (pintype "passive"))
      (node (ref "IC1") (pin "1") (pinfunction "IN8N_1") (pintype "input"))
      (node (ref "R49") (pin "2") (pinfunction "2_2") (pintype "passive"))
    )
    (net (code "34") (name "AIN8P") (class "Default")
      (node (ref "C48") (pin "1") (pinfunction "1_1") (pintype "passive"))
      (node (ref "IC1") (pin "2") (pinfunction "IN8P_2") (pintype "input"))
      (node (ref "R48") (pin "2") (pinfunction "2_2") (pintype "passive"))
    )
    (net (code "35") (name "ARD_SCL") (class "Default")
      (node (ref "IC9") (pin "P$1") (pinfunction "B2_P$1") (pintype "bidirectional"))
      (node (ref "JP22") (pin "8") (pinfunction "8_8") (pintype "passive"))
    )
    (net (code "36") (name "ARD_SDA") (class "Default")
      (node (ref "IC9") (pin "P$8") (pinfunction "B1_P$8") (pintype "bidirectional"))
      (node (ref "JP22") (pin "7") (pinfunction "7_7") (pintype "passive"))
    )
    (net (code "37") (name "AVDD") (class "Default")
      (node (ref "C10") (pin "1") (pinfunction "1_1") (pintype "passive"))
      (node (ref "C11") (pin "1") (pinfunction "1_1") (pintype "passive"))
      (node (ref "C12") (pin "1") (pinfunction "1_1") (pintype "passive"))
      (node (ref "C33") (pin "1") (pinfunction "1_1") (pintype "passive"))
      (node (ref "C50") (pin "1") (pinfunction "1_1") (pintype "passive"))
      (node (ref "C60") (pin "1") (pinfunction "1_1") (pintype "passive"))
      (node (ref "C7") (pin "1") (pinfunction "1_1") (pintype "passive"))
      (node (ref "C8") (pin "1") (pinfunction "1_1") (pintype "passive"))
      (node (ref "C9") (pin "1") (pinfunction "1_1") (pintype "passive"))
      (node (ref "IC1") (pin "19") (pinfunction "AVDD_19") (pintype "power_in"))
      (node (ref "IC1") (pin "21") (pinfunction "AVDD_21") (pintype "power_in"))
      (node (ref "IC1") (pin "22") (pinfunction "AVDD_22") (pintype "power_in"))
      (node (ref "IC1") (pin "54") (pinfunction "AVDD_54") (pintype "power_in"))
      (node (ref "IC1") (pin "56") (pinfunction "AVDD_56") (pintype "power_in"))
      (node (ref "IC1") (pin "59") (pinfunction "AVDD_59") (pintype "power_in"))
      (node (ref "IC7") (pin "5") (pinfunction "V_P_5") (pintype "bidirectional"))
      (node (ref "IC8") (pin "5") (pinfunction "V_P_5") (pintype "bidirectional"))
      (node (ref "JP16") (pin "2") (pinfunction "2_2") (pintype "passive"))
      (node (ref "JP4") (pin "2") (pinfunction "2_2") (pintype "passive"))
      (node (ref "R23") (pin "1") (pinfunction "1_1") (pintype "passive"))
      (node (ref "TP1") (pin "1") (pinfunction "1_1") (pintype "passive"))
    )
    (net (code "38") (name "AVSS") (class "Default")
      (node (ref "C11") (pin "2") (pinfunction "2_2") (pintype "passive"))
      (node (ref "C12") (pin "2") (pinfunction "2_2") (pintype "passive"))
      (node (ref "C17") (pin "2") (pinfunction "2_2") (pintype "passive"))
      (node (ref "C18") (pin "2") (pinfunction "2_2") (pintype "passive"))
      (node (ref "C19") (pin "2") (pinfunction "2_2") (pintype "passive"))
      (node (ref "C20") (pin "2") (pinfunction "2_2") (pintype "passive"))
      (node (ref "C21") (pin "2") (pinfunction "2_2") (pintype "passive"))
      (node (ref "C22") (pin "2") (pinfunction "2_2") (pintype "passive"))
      (node (ref "C23") (pin "2") (pinfunction "2_2") (pintype "passive"))
      (node (ref "C29") (pin "2") (pinfunction "2_2") (pintype "passive"))
      (node (ref "C30") (pin "2") (pinfunction "2_2") (pintype "passive"))
      (node (ref "C33") (pin "2") (pinfunction "2_2") (pintype "passive"))
      (node (ref "C51") (pin "2") (pinfunction "2_2") (pintype "passive"))
      (node (ref "C61") (pin "2") (pinfunction "2_2") (pintype "passive"))
      (node (ref "C7") (pin "2") (pinfunction "2_2") (pintype "passive"))
      (node (ref "C8") (pin "2") (pinfunction "2_2") (pintype "passive"))
      (node (ref "IC1") (pin "20") (pinfunction "AVSS_20") (pintype "power_in"))
      (node (ref "IC1") (pin "23") (pinfunction "AVSS_23") (pintype "power_in"))
      (node (ref "IC1") (pin "25") (pinfunction "VREFN_25") (pintype "bidirectional"))
      (node (ref "IC1") (pin "32") (pinfunction "AVSS_32") (pintype "power_in"))
      (node (ref "IC1") (pin "53") (pinfunction "AVSS1_53") (pintype "power_in"))
      (node (ref "IC1") (pin "57") (pinfunction "AVSS_57") (pintype "power_in"))
      (node (ref "IC1") (pin "58") (pinfunction "AVSS_58") (pintype "power_in"))
      (node (ref "IC7") (pin "2") (pinfunction "V_N_2") (pintype "bidirectional"))
      (node (ref "IC8") (pin "2") (pinfunction "V_N_2") (pintype "bidirectional"))
      (node (ref "JP5") (pin "2") (pinfunction "2_2") (pintype "passive"))
      (node (ref "R22") (pin "2") (pinfunction "2_2") (pintype "passive"))
      (node (ref "TP2") (pin "1") (pinfunction "1_1") (pintype "passive"))
    )
    (net (code "39") (name "BIASINV") (class "Default")
      (node (ref "C66") (pin "2") (pinfunction "2_2") (pintype "passive"))
      (node (ref "IC1") (pin "61") (pinfunction "BIASINV_61") (pintype "bidirectional"))
      (node (ref "JP15") (pin "1") (pinfunction "1_1") (pintype "passive"))
      (node (ref "JP16") (pin "3") (pinfunction "3_3") (pintype "passive"))
      (node (ref "R6") (pin "1") (pinfunction "1_1") (pintype "passive"))
    )
    (net (code "40") (name "BIASOUT") (class "Default")
      (node (ref "C66") (pin "1") (pinfunction "1_1") (pintype "passive"))
      (node (ref "IC1") (pin "63") (pinfunction "BIASOUT_63") (pintype "output"))
      (node (ref "R6") (pin "2") (pinfunction "2_2") (pintype "passive"))
      (node (ref "SJ1") (pin "1") (pinfunction "1_1") (pintype "passive"))
    )
    (net (code "41") (name "BIAS_ELEC") (class "Default")
      (node (ref "IC1") (pin "62") (pinfunction "BIASIN_62") (pintype "input"))
      (node (ref "JP6") (pin "1") (pinfunction "1_1") (pintype "passive"))
      (node (ref "R24") (pin "2") (pinfunction "2_2") (pintype "passive"))
    )
    (net (code "42") (name "BIAS_ELEC_CON") (class "Default")
      (node (ref "JP16") (pin "24") (pinfunction "24_24") (pintype "passive"))
      (node (ref "R24") (pin "1") (pinfunction "1_1") (pintype "passive"))
    )
    (net (code "43") (name "BOARD_ADDR_0") (class "Default")
      (node (ref "IC1") (pin "42") (pinfunction "GPIO1_42") (pintype "bidirectional"))
      (node (ref "IC5") (pin "1") (pinfunction "A0_1") (pintype "input"))
      (node (ref "JP3") (pin "3") (pinfunction "3_3") (pintype "passive"))
      (node (ref "R19") (pin "2") (pinfunction "2_2") (pintype "passive"))
    )
    (net (code "44") (name "BOARD_ADDR_1") (class "Default")
      (node (ref "IC1") (pin "44") (pinfunction "GPIO2_44") (pintype "bidirectional"))
      (node (ref "IC5") (pin "2") (pinfunction "A1_2") (pintype "input"))
      (node (ref "JP3") (pin "1") (pinfunction "1_1") (pintype "passive"))
      (node (ref "R20") (pin "2") (pinfunction "2_2") (pintype "passive"))
    )
    (net (code "45") (name "BOARD_ADDR_2") (class "Default")
      (node (ref "IC1") (pin "45") (pinfunction "GPIO3_45") (pintype "bidirectional"))
      (node (ref "IC5") (pin "3") (pinfunction "A2_3") (pintype "input"))
      (node (ref "R21") (pin "2") (pinfunction "2_2") (pintype "passive"))
    )
    (net (code "46") (name "CLK") (class "Default")
      (node (ref "IC1") (pin "37") (pinfunction "CLK_37") (pintype "input"))
      (node (ref "IC10") (pin "6") (pinfunction "A5_6") (pintype "bidirectional"))
    )
    (net (code "47") (name "CLKSEL") (class "Default")
      (node (ref "IC1") (pin "52") (pinfunction "CLKSEL_52") (pintype "input"))
      (node (ref "IC10") (pin "1") (pinfunction "A1_1") (pintype "bidirectional"))
    )
    (net (code "48") (name "DRDY") (class "Default")
      (node (ref "IC1") (pin "47") (pinfunction "~{DRDY}_47") (pintype "output"))
      (node (ref "IC10") (pin "3") (pinfunction "A2_3") (pintype "bidirectional"))
    )
    (net (code "49") (name "DVDD") (class "Default")
      (node (ref "C13") (pin "1") (pinfunction "1_1") (pintype "passive"))
      (node (ref "C14") (pin "1") (pinfunction "1_1") (pintype "passive"))
      (node (ref "C25") (pin "1") (pinfunction "1_1") (pintype "passive"))
      (node (ref "C52") (pin "2") (pinfunction "2_2") (pintype "passive"))
      (node (ref "C53") (pin "2") (pinfunction "2_2") (pintype "passive"))
      (node (ref "C56") (pin "2") (pinfunction "2_2") (pintype "passive"))
      (node (ref "C57") (pin "2") (pinfunction "2_2") (pintype "passive"))
      (node (ref "C63") (pin "1") (pinfunction "1_1") (pintype "passive"))
      (node (ref "C70") (pin "2") (pinfunction "2_2") (pintype "passive"))
      (node (ref "C71") (pin "2") (pinfunction "2_2") (pintype "passive"))
      (node (ref "IC1") (pin "48") (pinfunction "DVDD_48") (pintype "power_in"))
      (node (ref "IC1") (pin "50") (pinfunction "DVDD_50") (pintype "power_in"))
      (node (ref "IC10") (pin "2") (pinfunction "VCCA_2") (pintype "bidirectional"))
      (node (ref "IC11") (pin "2") (pinfunction "VCCA_2") (pintype "bidirectional"))
      (node (ref "IC5") (pin "8") (pinfunction "VCC_8") (pintype "power_in"))
      (node (ref "IC9") (pin "P$3") (pinfunction "VCCA_P$3") (pintype "bidirectional"))
      (node (ref "JP16") (pin "1") (pinfunction "1_1") (pintype "passive"))
      (node (ref "JP26") (pin "4") (pinfunction "4_4") (pintype "passive"))
      (node (ref "JP3") (pin "2") (pinfunction "2_2") (pintype "passive"))
      (node (ref "JP3") (pin "4") (pinfunction "4_4") (pintype "passive"))
      (node (ref "R1") (pin "1") (pinfunction "1_1") (pintype "passive"))
      (node (ref "R2") (pin "1") (pinfunction "1_1") (pintype "passive"))
      (node (ref "R3") (pin "1") (pinfunction "1_1") (pintype "passive"))
      (node (ref "R4") (pin "1") (pinfunction "1_1") (pintype "passive"))
    )
    (net (code "50") (name "GPIO4") (class "Default")
      (node (ref "IC1") (pin "46") (pinfunction "GPIO4_46") (pintype "bidirectional"))
      (node (ref "R18") (pin "1") (pinfunction "1_1") (pintype "passive"))
    )
    (net (code "51") (name "IN1N") (class "Default")
      (node (ref "JP16") (pin "8") (pinfunction "8_8") (pintype "passive"))
      (node (ref "R35") (pin "1") (pinfunction "1_1") (pintype "passive"))
    )
    (net (code "52") (name "IN1P") (class "Default")
      (node (ref "JP16") (pin "7") (pinfunction "7_7") (pintype "passive"))
      (node (ref "R34") (pin "1") (pinfunction "1_1") (pintype "passive"))
    )
    (net (code "53") (name "IN2N") (class "Default")
      (node (ref "JP16") (pin "10") (pinfunction "10_10") (pintype "passive"))
      (node (ref "R37") (pin "1") (pinfunction "1_1") (pintype "passive"))
    )
    (net (code "54") (name "IN2P") (class "Default")
      (node (ref "JP16") (pin "9") (pinfunction "9_9") (pintype "passive"))
      (node (ref "R36") (pin "1") (pinfunction "1_1") (pintype "passive"))
    )
    (net (code "55") (name "IN3N") (class "Default")
      (node (ref "JP16") (pin "12") (pinfunction "12_12") (pintype "passive"))
      (node (ref "R39") (pin "1") (pinfunction "1_1") (pintype "passive"))
    )
    (net (code "56") (name "IN3P") (class "Default")
      (node (ref "JP16") (pin "11") (pinfunction "11_11") (pintype "passive"))
      (node (ref "R38") (pin "1") (pinfunction "1_1") (pintype "passive"))
    )
    (net (code "57") (name "IN4N") (class "Default")
      (node (ref "JP16") (pin "14") (pinfunction "14_14") (pintype "passive"))
      (node (ref "R41") (pin "1") (pinfunction "1_1") (pintype "passive"))
    )
    (net (code "58") (name "IN4P") (class "Default")
      (node (ref "JP16") (pin "13") (pinfunction "13_13") (pintype "passive"))
      (node (ref "R40") (pin "1") (pinfunction "1_1") (pintype "passive"))
    )
    (net (code "59") (name "IN5N") (class "Default")
      (node (ref "JP16") (pin "16") (pinfunction "16_16") (pintype "passive"))
      (node (ref "R43") (pin "1") (pinfunction "1_1") (pintype "passive"))
    )
    (net (code "60") (name "IN5P") (class "Default")
      (node (ref "JP16") (pin "15") (pinfunction "15_15") (pintype "passive"))
      (node (ref "R42") (pin "1") (pinfunction "1_1") (pintype "passive"))
    )
    (net (code "61") (name "IN6N") (class "Default")
      (node (ref "JP16") (pin "18") (pinfunction "18_18") (pintype "passive"))
      (node (ref "R45") (pin "1") (pinfunction "1_1") (pintype "passive"))
    )
    (net (code "62") (name "IN6P") (class "Default")
      (node (ref "JP16") (pin "17") (pinfunction "17_17") (pintype "passive"))
      (node (ref "R44") (pin "1") (pinfunction "1_1") (pintype "passive"))
    )
    (net (code "63") (name "IN7N") (class "Default")
      (node (ref "JP16") (pin "20") (pinfunction "20_20") (pintype "passive"))
      (node (ref "R47") (pin "1") (pinfunction "1_1") (pintype "passive"))
    )
    (net (code "64") (name "IN7P") (class "Default")
      (node (ref "JP16") (pin "19") (pinfunction "19_19") (pintype "passive"))
      (node (ref "R46") (pin "1") (pinfunction "1_1") (pintype "passive"))
    )
    (net (code "65") (name "IN8N") (class "Default")
      (node (ref "JP16") (pin "22") (pinfunction "22_22") (pintype "passive"))
      (node (ref "R49") (pin "1") (pinfunction "1_1") (pintype "passive"))
    )
    (net (code "66") (name "IN8P") (class "Default")
      (node (ref "JP16") (pin "21") (pinfunction "21_21") (pintype "passive"))
      (node (ref "R48") (pin "1") (pinfunction "1_1") (pintype "passive"))
    )
    (net (code "67") (name "IOREF") (class "Default")
      (node (ref "C54") (pin "2") (pinfunction "2_2") (pintype "passive"))
      (node (ref "C55") (pin "2") (pinfunction "2_2") (pintype "passive"))
      (node (ref "C58") (pin "2") (pinfunction "2_2") (pintype "passive"))
      (node (ref "C59") (pin "2") (pinfunction "2_2") (pintype "passive"))
      (node (ref "C72") (pin "2") (pinfunction "2_2") (pintype "passive"))
      (node (ref "C73") (pin "2") (pinfunction "2_2") (pintype "passive"))
      (node (ref "IC10") (pin "19") (pinfunction "VCCB_19") (pintype "bidirectional"))
      (node (ref "IC11") (pin "19") (pinfunction "VCCB_19") (pintype "bidirectional"))
      (node (ref "IC9") (pin "P$7") (pinfunction "VCCB_P$7") (pintype "bidirectional"))
      (node (ref "JP26") (pin "2") (pinfunction "2_2") (pintype "passive"))
    )
    (net (code "68") (name "Net-(D1-PadA)") (class "Default")
      (node (ref "D1") (pin "A") (pinfunction "A_A") (pintype "passive"))
      (node (ref "R1") (pin "2") (pinfunction "2_2") (pintype "passive"))
    )
    (net (code "69") (name "Net-(D2-PadA)") (class "Default")
      (node (ref "D2") (pin "A") (pinfunction "A_A") (pintype "passive"))
      (node (ref "R18") (pin "2") (pinfunction "2_2") (pintype "passive"))
    )
    (net (code "70") (name "Net-(IC1-VCAP1)") (class "Default")
      (node (ref "C17") (pin "1") (pinfunction "1_1") (pintype "passive"))
      (node (ref "IC1") (pin "28") (pinfunction "VCAP1_28") (pintype "bidirectional"))
    )
    (net (code "71") (name "Net-(IC1-VCAP2)") (class "Default")
      (node (ref "C18") (pin "1") (pinfunction "1_1") (pintype "passive"))
      (node (ref "IC1") (pin "30") (pinfunction "VCAP2_30") (pintype "bidirectional"))
    )
    (net (code "72") (name "Net-(IC1-VCAP3)") (class "Default")
      (node (ref "C19") (pin "1") (pinfunction "1_1") (pintype "passive"))
      (node (ref "C20") (pin "1") (pinfunction "1_1") (pintype "passive"))
      (node (ref "IC1") (pin "55") (pinfunction "VCAP3_55") (pintype "bidirectional"))
    )
    (net (code "73") (name "Net-(IC1-VCAP4)") (class "Default")
      (node (ref "C21") (pin "1") (pinfunction "1_1") (pintype "passive"))
      (node (ref "IC1") (pin "26") (pinfunction "VCAP4_26") (pintype "bidirectional"))
    )
    (net (code "74") (name "Net-(IC2-NR{slash}FB)") (class "Default")
      (node (ref "C31") (pin "1") (pinfunction "1_1") (pintype "passive"))
      (node (ref "IC2") (pin "4") (pinfunction "NR/FB_4") (pintype "bidirectional"))
    )
    (net (code "75") (name "Net-(IC2-OUT)") (class "Default")
      (node (ref "C1") (pin "1") (pinfunction "1_1") (pintype "passive"))
      (node (ref "C2") (pin "1") (pinfunction "1_1") (pintype "passive"))
      (node (ref "IC2") (pin "5") (pinfunction "OUT_5") (pintype "bidirectional"))
      (node (ref "L1") (pin "1") (pinfunction "1_1") (pintype "passive"))
    )
    (net (code "76") (name "Net-(IC3-NR{slash}FB)") (class "Default")
      (node (ref "C32") (pin "1") (pinfunction "1_1") (pintype "passive"))
      (node (ref "IC3") (pin "4") (pinfunction "NR/FB_4") (pintype "bidirectional"))
    )
    (net (code "77") (name "Net-(IC3-OUT)") (class "Default")
      (node (ref "C4") (pin "1") (pinfunction "1_1") (pintype "passive"))
      (node (ref "C5") (pin "1") (pinfunction "1_1") (pintype "passive"))
      (node (ref "IC3") (pin "5") (pinfunction "OUT_5") (pintype "bidirectional"))
      (node (ref "L2") (pin "1") (pinfunction "1_1") (pintype "passive"))
    )
    (net (code "78") (name "Net-(IC6-CFLY_N)") (class "Default")
      (node (ref "C26") (pin "1") (pinfunction "1_1") (pintype "passive"))
      (node (ref "IC6") (pin "3") (pinfunction "CFLY_N_3") (pintype "bidirectional"))
    )
    (net (code "79") (name "Net-(IC6-CFLY_P)") (class "Default")
      (node (ref "C26") (pin "2") (pinfunction "2_2") (pintype "passive"))
      (node (ref "IC6") (pin "5") (pinfunction "CFLY_P_5") (pintype "bidirectional"))
    )
    (net (code "80") (name "Net-(IC6-OUT)") (class "Default")
      (node (ref "C15") (pin "1") (pinfunction "1_1") (pintype "passive"))
      (node (ref "C16") (pin "1") (pinfunction "1_1") (pintype "passive"))
      (node (ref "IC6") (pin "1") (pinfunction "OUT_1") (pintype "bidirectional"))
      (node (ref "L3") (pin "1") (pinfunction "1_1") (pintype "passive"))
    )
    (net (code "81") (name "Net-(IC7-N_IN)") (class "Default")
      (node (ref "IC7") (pin "1") (pinfunction "OUT_1") (pintype "bidirectional"))
      (node (ref "IC7") (pin "4") (pinfunction "N_IN_4") (pintype "bidirectional"))
      (node (ref "JP6") (pin "3") (pinfunction "3_3") (pintype "passive"))
    )
    (net (code "82") (name "Net-(IC7-P_IN)") (class "Default")
      (node (ref "IC7") (pin "3") (pinfunction "P_IN_3") (pintype "bidirectional"))
      (node (ref "R22") (pin "1") (pinfunction "1_1") (pintype "passive"))
      (node (ref "R23") (pin "2") (pinfunction "2_2") (pintype "passive"))
    )
    (net (code "83") (name "Net-(IC8-N_IN)") (class "Default")
      (node (ref "IC8") (pin "1") (pinfunction "OUT_1") (pintype "bidirectional"))
      (node (ref "IC8") (pin "4") (pinfunction "N_IN_4") (pintype "bidirectional"))
      (node (ref "JP8") (pin "3") (pinfunction "3_3") (pintype "passive"))
    )
    (net (code "84") (name "Net-(IC8-P_IN)") (class "Default")
      (node (ref "IC8") (pin "3") (pinfunction "P_IN_3") (pintype "bidirectional"))
      (node (ref "JP7") (pin "2") (pinfunction "2_2") (pintype "passive"))
    )
    (net (code "85") (name "Net-(IC9-OE)") (class "Default")
      (node (ref "IC9") (pin "P$6") (pinfunction "OE_P$6") (pintype "bidirectional"))
      (node (ref "R4") (pin "2") (pinfunction "2_2") (pintype "passive"))
    )
    (net (code "86") (name "Net-(IC10-OE)") (class "Default")
      (node (ref "IC10") (pin "10") (pinfunction "OE_10") (pintype "bidirectional"))
      (node (ref "R2") (pin "2") (pinfunction "2_2") (pintype "passive"))
    )
    (net (code "87") (name "Net-(IC11-OE)") (class "Default")
      (node (ref "IC11") (pin "10") (pinfunction "OE_10") (pintype "bidirectional"))
      (node (ref "R3") (pin "2") (pinfunction "2_2") (pintype "passive"))
    )
    (net (code "88") (name "REF_ELEC") (class "Default")
      (node (ref "C62") (pin "1") (pinfunction "1_1") (pintype "passive"))
      (node (ref "JP7") (pin "1") (pinfunction "1_1") (pintype "passive"))
      (node (ref "JP8") (pin "1") (pinfunction "1_1") (pintype "passive"))
      (node (ref "R25") (pin "1") (pinfunction "1_1") (pintype "passive"))
    )
    (net (code "89") (name "REF_ELEC_CON") (class "Default")
      (node (ref "JP16") (pin "23") (pinfunction "23_23") (pintype "passive"))
      (node (ref "R25") (pin "2") (pinfunction "2_2") (pintype "passive"))
    )
    (net (code "90") (name "RESET") (class "Default")
      (node (ref "SPI") (pin "5") (pinfunction "5_5") (pintype "passive"))
    )
    (net (code "91") (name "SCL") (class "Default")
      (node (ref "IC5") (pin "6") (pinfunction "SCL_6") (pintype "input"))
      (node (ref "IC9") (pin "P$4") (pinfunction "A2_P$4") (pintype "bidirectional"))
    )
    (net (code "92") (name "SDA") (class "Default")
      (node (ref "IC5") (pin "5") (pinfunction "SDA_5") (pintype "bidirectional"))
      (node (ref "IC9") (pin "P$5") (pinfunction "A1_P$5") (pintype "bidirectional"))
    )
    (net (code "93") (name "SPI0_MISO") (class "Default")
      (node (ref "JP2") (pin "2") (pinfunction "2_2") (pintype "passive"))
      (node (ref "SPI") (pin "1") (pinfunction "1_1") (pintype "passive"))
    )
    (net (code "94") (name "SPI0_MOSI") (class "Default")
      (node (ref "JP2") (pin "18") (pinfunction "18_18") (pintype "passive"))
      (node (ref "SPI") (pin "4") (pinfunction "4_4") (pintype "passive"))
    )
    (net (code "95") (name "SPI0_SCK") (class "Default")
      (node (ref "JP2") (pin "8") (pinfunction "8_8") (pintype "passive"))
      (node (ref "SPI") (pin "3") (pinfunction "3_3") (pintype "passive"))
    )
    (net (code "96") (name "SPI_CLK") (class "Default")
      (node (ref "IC1") (pin "40") (pinfunction "SCLK_40") (pintype "input"))
      (node (ref "IC10") (pin "5") (pinfunction "A4_5") (pintype "bidirectional"))
    )
    (net (code "97") (name "SPI_IN") (class "Default")
      (node (ref "IC1") (pin "34") (pinfunction "DIN_34") (pintype "input"))
      (node (ref "IC10") (pin "7") (pinfunction "A6_7") (pintype "bidirectional"))
    )
    (net (code "98") (name "SPI_OUT") (class "Default")
      (node (ref "IC1") (pin "43") (pinfunction "DOUT_43") (pintype "output"))
      (node (ref "IC10") (pin "4") (pinfunction "A3_4") (pintype "bidirectional"))
    )
    (net (code "99") (name "SRB1") (class "Default")
      (node (ref "IC1") (pin "18") (pinfunction "SRB2_18") (pintype "output"))
      (node (ref "JP6") (pin "2") (pinfunction "2_2") (pintype "passive"))
      (node (ref "JP8") (pin "2") (pinfunction "2_2") (pintype "passive"))
    )
    (net (code "100") (name "SRB2") (class "Default")
      (node (ref "IC1") (pin "17") (pinfunction "SRB1_17") (pintype "output"))
      (node (ref "JP7") (pin "3") (pinfunction "3_3") (pintype "passive"))
    )
    (net (code "101") (name "START") (class "Default")
      (node (ref "IC1") (pin "38") (pinfunction "START_38") (pintype "input"))
      (node (ref "IC11") (pin "3") (pinfunction "A2_3") (pintype "bidirectional"))
    )
    (net (code "102") (name "SYNC_CONN_2") (class "Default")
      (node (ref "JP15") (pin "2") (pinfunction "2_2") (pintype "passive"))
      (node (ref "SJ1") (pin "2") (pinfunction "2_2") (pintype "passive"))
      (node (ref "SJ2") (pin "2") (pinfunction "2_2") (pintype "passive"))
    )
    (net (code "103") (name "USART1_MISO") (class "Default")
      (node (ref "JP2") (pin "4") (pinfunction "4_4") (pintype "passive"))
      (node (ref "JP22") (pin "4") (pinfunction "4_4") (pintype "passive"))
    )
    (net (code "104") (name "USART1_MOSI") (class "Default")
      (node (ref "JP2") (pin "20") (pinfunction "20_20") (pintype "passive"))
      (node (ref "JP22") (pin "3") (pinfunction "3_3") (pintype "passive"))
    )
    (net (code "105") (name "USART1_SCK") (class "Default")
      (node (ref "JP2") (pin "6") (pinfunction "6_6") (pintype "passive"))
      (node (ref "JP25") (pin "1") (pinfunction "1_1") (pintype "passive"))
    )
    (net (code "106") (name "VCC_-5V") (class "Default")
      (node (ref "C24") (pin "1") (pinfunction "1_1") (pintype "passive"))
      (node (ref "C28") (pin "1") (pinfunction "1_1") (pintype "passive"))
      (node (ref "IC2") (pin "2") (pinfunction "IN_2") (pintype "bidirectional"))
      (node (ref "IC2") (pin "3") (pinfunction "EN_3") (pintype "bidirectional"))
      (node (ref "L3") (pin "2") (pinfunction "2_2") (pintype "passive"))
    )
    (net (code "107") (name "VCC_5V") (class "Default")
      (node (ref "C27") (pin "1") (pinfunction "1_1") (pintype "passive"))
      (node (ref "L4") (pin "1") (pinfunction "1_1") (pintype "passive"))
      (node (ref "SPI") (pin "2") (pinfunction "2_2") (pintype "passive"))
    )
    (net (code "108") (name "VCC_5V_FILTERED") (class "Default")
      (node (ref "C64") (pin "1") (pinfunction "1_1") (pintype "passive"))
      (node (ref "C65") (pin "1") (pinfunction "1_1") (pintype "passive"))
      (node (ref "C68") (pin "1") (pinfunction "1_1") (pintype "passive"))
      (node (ref "IC3") (pin "1") (pinfunction "IN_1") (pintype "bidirectional"))
      (node (ref "IC3") (pin "3") (pinfunction "EN_3") (pintype "bidirectional"))
      (node (ref "IC6") (pin "2") (pinfunction "IN_2") (pintype "bidirectional"))
      (node (ref "JP4") (pin "1") (pinfunction "1_1") (pintype "passive"))
      (node (ref "L4") (pin "2") (pinfunction "2_2") (pintype "passive"))
    )
    (net (code "109") (name "VREFP") (class "Default")
      (node (ref "C22") (pin "1") (pinfunction "1_1") (pintype "passive"))
      (node (ref "C23") (pin "1") (pinfunction "1_1") (pintype "passive"))
      (node (ref "IC1") (pin "24") (pinfunction "VREFP_24") (pintype "bidirectional"))
      (node (ref "TP4") (pin "1") (pinfunction "1_1") (pintype "passive"))
    )
    (net (code "110") (name "unconnected-(IC1-BIASREF-Pad60)") (class "Default")
      (node (ref "IC1") (pin "60") (pinfunction "BIASREF_60") (pintype "input"))
    )
    (net (code "111") (name "unconnected-(IC1-NC-Pad27)") (class "Default")
      (node (ref "IC1") (pin "27") (pinfunction "NC_27") (pintype "no_connect"))
    )
    (net (code "112") (name "unconnected-(IC1-NC-Pad29)") (class "Default")
      (node (ref "IC1") (pin "29") (pinfunction "NC_29") (pintype "no_connect"))
    )
    (net (code "113") (name "unconnected-(IC1-NC-Pad64)") (class "Default")
      (node (ref "IC1") (pin "64") (pinfunction "NC_64") (pintype "no_connect"))
    )
    (net (code "114") (name "unconnected-(IC1-RESV1-Pad31)") (class "Default")
      (node (ref "IC1") (pin "31") (pinfunction "RESV1_31") (pintype "no_connect"))
    )
    (net (code "115") (name "unconnected-(JP3-Pad5)") (class "Default")
      (node (ref "JP3") (pin "5") (pinfunction "5_5") (pintype "passive"))
    )
    (net (code "116") (name "unconnected-(JP3-Pad6)") (class "Default")
      (node (ref "JP3") (pin "6") (pinfunction "6_6") (pintype "passive"))
    )
    (net (code "117") (name "unconnected-(JP3-Pad7)") (class "Default")
      (node (ref "JP3") (pin "7") (pinfunction "7_7") (pintype "passive"))
    )
    (net (code "118") (name "unconnected-(JP3-Pad8)") (class "Default")
      (node (ref "JP3") (pin "8") (pinfunction "8_8") (pintype "passive"))
    )
    (net (code "119") (name "unconnected-(JP20-Pad1)") (class "Default")
      (node (ref "JP20") (pin "1") (pinfunction "1_1") (pintype "passive"))
    )
    (net (code "120") (name "unconnected-(JP20-Pad2)") (class "Default")
      (node (ref "JP20") (pin "2") (pinfunction "2_2") (pintype "passive"))
    )
    (net (code "121") (name "unconnected-(JP20-Pad3)") (class "Default")
      (node (ref "JP20") (pin "3") (pinfunction "3_3") (pintype "passive"))
    )
    (net (code "122") (name "unconnected-(JP20-Pad4)") (class "Default")
      (node (ref "JP20") (pin "4") (pinfunction "4_4") (pintype "passive"))
    )
    (net (code "123") (name "unconnected-(JP20-Pad5)") (class "Default")
      (node (ref "JP20") (pin "5") (pinfunction "5_5") (pintype "passive"))
    )
    (net (code "124") (name "unconnected-(JP20-Pad6)") (class "Default")
      (node (ref "JP20") (pin "6") (pinfunction "6_6") (pintype "passive"))
    )
    (net (code "125") (name "unconnected-(JP20-Pad7)") (class "Default")
      (node (ref "JP20") (pin "7") (pinfunction "7_7") (pintype "passive"))
    )
    (net (code "126") (name "unconnected-(JP20-Pad9)") (class "Default")
      (node (ref "JP20") (pin "9") (pinfunction "9_9") (pintype "passive"))
    )
    (net (code "127") (name "unconnected-(JP20-Pad10)") (class "Default")
      (node (ref "JP20") (pin "10") (pinfunction "10_10") (pintype "passive"))
    )
    (net (code "128") (name "unconnected-(JP21-Pad1)") (class "Default")
      (node (ref "JP21") (pin "1") (pinfunction "1_1") (pintype "passive"))
    )
    (net (code "129") (name "unconnected-(JP21-Pad2)") (class "Default")
      (node (ref "JP21") (pin "2") (pinfunction "2_2") (pintype "passive"))
    )
    (net (code "130") (name "unconnected-(JP21-Pad3)") (class "Default")
      (node (ref "JP21") (pin "3") (pinfunction "3_3") (pintype "passive"))
    )
    (net (code "131") (name "unconnected-(JP21-Pad5)") (class "Default")
      (node (ref "JP21") (pin "5") (pinfunction "5_5") (pintype "passive"))
    )
    (net (code "132") (name "unconnected-(JP21-Pad6)") (class "Default")
      (node (ref "JP21") (pin "6") (pinfunction "6_6") (pintype "passive"))
    )
    (net (code "133") (name "unconnected-(JP21-Pad7)") (class "Default")
      (node (ref "JP21") (pin "7") (pinfunction "7_7") (pintype "passive"))
    )
    (net (code "134") (name "unconnected-(JP21-Pad8)") (class "Default")
      (node (ref "JP21") (pin "8") (pinfunction "8_8") (pintype "passive"))
    )
    (net (code "135") (name "unconnected-(JP22-Pad1)") (class "Default")
      (node (ref "JP22") (pin "1") (pinfunction "1_1") (pintype "passive"))
    )
    (net (code "136") (name "unconnected-(JP22-Pad2)") (class "Default")
      (node (ref "JP22") (pin "2") (pinfunction "2_2") (pintype "passive"))
    )
    (net (code "137") (name "unconnected-(JP22-Pad5)") (class "Default")
      (node (ref "JP22") (pin "5") (pinfunction "5_5") (pintype "passive"))
    )
    (net (code "138") (name "unconnected-(JP22-Pad6)") (class "Default")
      (node (ref "JP22") (pin "6") (pinfunction "6_6") (pintype "passive"))
    )
    (net (code "139") (name "unconnected-(JP23-Pad1)") (class "Default")
      (node (ref "JP23") (pin "1") (pinfunction "1_1") (pintype "passive"))
    )
    (net (code "140") (name "unconnected-(JP23-Pad2)") (class "Default")
      (node (ref "JP23") (pin "2") (pinfunction "2_2") (pintype "passive"))
    )
    (net (code "141") (name "unconnected-(JP23-Pad3)") (class "Default")
      (node (ref "JP23") (pin "3") (pinfunction "3_3") (pintype "passive"))
    )
    (net (code "142") (name "unconnected-(JP23-Pad9)") (class "Default")
      (node (ref "JP23") (pin "9") (pinfunction "9_9") (pintype "passive"))
    )
    (net (code "143") (name "unconnected-(JP23-Pad10)") (class "Default")
      (node (ref "JP23") (pin "10") (pinfunction "10_10") (pintype "passive"))
    )
    (net (code "144") (name "unconnected-(JP23-Pad15)") (class "Default")
      (node (ref "JP23") (pin "15") (pinfunction "15_15") (pintype "passive"))
    )
    (net (code "145") (name "unconnected-(JP23-Pad16)") (class "Default")
      (node (ref "JP23") (pin "16") (pinfunction "16_16") (pintype "passive"))
    )
    (net (code "146") (name "unconnected-(JP23-Pad17)") (class "Default")
      (node (ref "JP23") (pin "17") (pinfunction "17_17") (pintype "passive"))
    )
    (net (code "147") (name "unconnected-(JP23-Pad18)") (class "Default")
      (node (ref "JP23") (pin "18") (pinfunction "18_18") (pintype "passive"))
    )
    (net (code "148") (name "unconnected-(JP23-Pad19)") (class "Default")
      (node (ref "JP23") (pin "19") (pinfunction "19_19") (pintype "passive"))
    )
    (net (code "149") (name "unconnected-(JP23-Pad20)") (class "Default")
      (node (ref "JP23") (pin "20") (pinfunction "20_20") (pintype "passive"))
    )
    (net (code "150") (name "unconnected-(JP23-Pad21)") (class "Default")
      (node (ref "JP23") (pin "21") (pinfunction "21_21") (pintype "passive"))
    )
    (net (code "151") (name "unconnected-(JP23-Pad22)") (class "Default")
      (node (ref "JP23") (pin "22") (pinfunction "22_22") (pintype "passive"))
    )
    (net (code "152") (name "unconnected-(JP23-Pad23)") (class "Default")
      (node (ref "JP23") (pin "23") (pinfunction "23_23") (pintype "passive"))
    )
    (net (code "153") (name "unconnected-(JP23-Pad24)") (class "Default")
      (node (ref "JP23") (pin "24") (pinfunction "24_24") (pintype "passive"))
    )
    (net (code "154") (name "unconnected-(JP23-Pad25)") (class "Default")
      (node (ref "JP23") (pin "25") (pinfunction "25_25") (pintype "passive"))
    )
    (net (code "155") (name "unconnected-(JP23-Pad26)") (class "Default")
      (node (ref "JP23") (pin "26") (pinfunction "26_26") (pintype "passive"))
    )
    (net (code "156") (name "unconnected-(JP23-Pad30)") (class "Default")
      (node (ref "JP23") (pin "30") (pinfunction "30_30") (pintype "passive"))
    )
    (net (code "157") (name "unconnected-(JP23-Pad31)") (class "Default")
      (node (ref "JP23") (pin "31") (pinfunction "31_31") (pintype "passive"))
    )
    (net (code "158") (name "unconnected-(JP23-Pad32)") (class "Default")
      (node (ref "JP23") (pin "32") (pinfunction "32_32") (pintype "passive"))
    )
    (net (code "159") (name "unconnected-(JP23-Pad34)") (class "Default")
      (node (ref "JP23") (pin "34") (pinfunction "34_34") (pintype "passive"))
    )
    (net (code "160") (name "unconnected-(JP24-Pad1)") (class "Default")
      (node (ref "JP24") (pin "1") (pinfunction "1_1") (pintype "passive"))
    )
    (net (code "161") (name "unconnected-(JP24-Pad2)") (class "Default")
      (node (ref "JP24") (pin "2") (pinfunction "2_2") (pintype "passive"))
    )
    (net (code "162") (name "unconnected-(JP24-Pad3)") (class "Default")
      (node (ref "JP24") (pin "3") (pinfunction "3_3") (pintype "passive"))
    )
    (net (code "163") (name "unconnected-(JP24-Pad4)") (class "Default")
      (node (ref "JP24") (pin "4") (pinfunction "4_4") (pintype "passive"))
    )
    (net (code "164") (name "unconnected-(JP24-Pad5)") (class "Default")
      (node (ref "JP24") (pin "5") (pinfunction "5_5") (pintype "passive"))
    )
    (net (code "165") (name "unconnected-(JP24-Pad6)") (class "Default")
      (node (ref "JP24") (pin "6") (pinfunction "6_6") (pintype "passive"))
    )
    (net (code "166") (name "unconnected-(JP24-Pad7)") (class "Default")
      (node (ref "JP24") (pin "7") (pinfunction "7_7") (pintype "passive"))
    )
    (net (code "167") (name "unconnected-(JP24-Pad8)") (class "Default")
      (node (ref "JP24") (pin "8") (pinfunction "8_8") (pintype "passive"))
    )
    (net (code "168") (name "unconnected-(JP25-Pad2)") (class "Default")
      (node (ref "JP25") (pin "2") (pinfunction "2_2") (pintype "passive"))
    )
    (net (code "169") (name "unconnected-(JP25-Pad3)") (class "Default")
      (node (ref "JP25") (pin "3") (pinfunction "3_3") (pintype "passive"))
    )
    (net (code "170") (name "unconnected-(JP25-Pad4)") (class "Default")
      (node (ref "JP25") (pin "4") (pinfunction "4_4") (pintype "passive"))
    )
    (net (code "171") (name "unconnected-(JP25-Pad6)") (class "Default")
      (node (ref "JP25") (pin "6") (pinfunction "6_6") (pintype "passive"))
    )
    (net (code "172") (name "unconnected-(JP25-Pad7)") (class "Default")
      (node (ref "JP25") (pin "7") (pinfunction "7_7") (pintype "passive"))
    )
    (net (code "173") (name "unconnected-(JP26-Pad1)") (class "Default")
      (node (ref "JP26") (pin "1") (pinfunction "1_1") (pintype "passive"))
    )
    (net (code "174") (name "unconnected-(JP26-Pad3)") (class "Default")
      (node (ref "JP26") (pin "3") (pinfunction "3_3") (pintype "passive"))
    )
    (net (code "175") (name "unconnected-(JP26-Pad5)") (class "Default")
      (node (ref "JP26") (pin "5") (pinfunction "5_5") (pintype "passive"))
    )
    (net (code "176") (name "unconnected-(JP26-Pad6)") (class "Default")
      (node (ref "JP26") (pin "6") (pinfunction "6_6") (pintype "passive"))
    )
    (net (code "177") (name "unconnected-(JP26-Pad7)") (class "Default")
      (node (ref "JP26") (pin "7") (pinfunction "7_7") (pintype "passive"))
    )
    (net (code "178") (name "unconnected-(JP26-Pad8)") (class "Default")
      (node (ref "JP26") (pin "8") (pinfunction "8_8") (pintype "passive"))
    )
    (net (code "179") (name "~{ADC_CS_0}") (class "Default")
      (node (ref "JP2") (pin "10") (pinfunction "10_10") (pintype "passive"))
      (node (ref "JP21") (pin "4") (pinfunction "4_4") (pintype "passive"))
    )
    (net (code "180") (name "~{ADC_CS_1}") (class "Default")
      (node (ref "JP2") (pin "12") (pinfunction "12_12") (pintype "passive"))
      (node (ref "JP20") (pin "8") (pinfunction "8_8") (pintype "passive"))
    )
    (net (code "181") (name "~{ADC_CS_2}") (class "Default")
      (node (ref "JP2") (pin "14") (pinfunction "14_14") (pintype "passive"))
      (node (ref "JP23") (pin "33") (pinfunction "33_33") (pintype "passive"))
    )
    (net (code "182") (name "~{ADC_CS_3}") (class "Default")
      (node (ref "JP2") (pin "16") (pinfunction "16_16") (pintype "passive"))
      (node (ref "JP23") (pin "4") (pinfunction "4_4") (pintype "passive"))
    )
    (net (code "183") (name "~{ADC_PWDN_0}") (class "Default")
      (node (ref "JP1") (pin "22") (pinfunction "22_22") (pintype "passive"))
      (node (ref "JP23") (pin "13") (pinfunction "13_13") (pintype "passive"))
    )
    (net (code "184") (name "~{ADC_PWDN_1}") (class "Default")
      (node (ref "JP1") (pin "24") (pinfunction "24_24") (pintype "passive"))
      (node (ref "JP23") (pin "14") (pinfunction "14_14") (pintype "passive"))
    )
    (net (code "185") (name "~{ADC_RESET_0}") (class "Default")
      (node (ref "JP1") (pin "18") (pinfunction "18_18") (pintype "passive"))
      (node (ref "JP23") (pin "27") (pinfunction "27_27") (pintype "passive"))
    )
    (net (code "186") (name "~{ADC_RESET_1}") (class "Default")
      (node (ref "JP1") (pin "20") (pinfunction "20_20") (pintype "passive"))
      (node (ref "JP23") (pin "28") (pinfunction "28_28") (pintype "passive"))
    )
    (net (code "187") (name "~{ADS_PWDN}") (class "Default")
      (node (ref "IC11") (pin "15") (pinfunction "B5_15") (pintype "bidirectional"))
      (node (ref "JP1") (pin "21") (pinfunction "21_21") (pintype "passive"))
      (node (ref "JP1") (pin "23") (pinfunction "23_23") (pintype "passive"))
    )
    (net (code "188") (name "~{ADS_RESET}") (class "Default")
      (node (ref "IC11") (pin "20") (pinfunction "B1_20") (pintype "bidirectional"))
      (node (ref "JP1") (pin "17") (pinfunction "17_17") (pintype "passive"))
      (node (ref "JP1") (pin "19") (pinfunction "19_19") (pintype "passive"))
    )
    (net (code "189") (name "~{ADS_SPI_CS}") (class "Default")
      (node (ref "IC11") (pin "14") (pinfunction "B6_14") (pintype "bidirectional"))
      (node (ref "JP2") (pin "11") (pinfunction "11_11") (pintype "passive"))
      (node (ref "JP2") (pin "13") (pinfunction "13_13") (pintype "passive"))
      (node (ref "JP2") (pin "15") (pinfunction "15_15") (pintype "passive"))
      (node (ref "JP2") (pin "9") (pinfunction "9_9") (pintype "passive"))
    )
    (net (code "190") (name "~{PWDN}") (class "Default")
      (node (ref "IC1") (pin "35") (pinfunction "~{PWDN}_35") (pintype "input"))
      (node (ref "IC11") (pin "6") (pinfunction "A5_6") (pintype "bidirectional"))
    )
    (net (code "191") (name "~{RESET}") (class "Default")
      (node (ref "IC1") (pin "36") (pinfunction "~{RESET}_36") (pintype "input"))
      (node (ref "IC11") (pin "1") (pinfunction "A1_1") (pintype "bidirectional"))
    )
    (net (code "192") (name "~{SPI_CS}") (class "Default")
      (node (ref "IC1") (pin "39") (pinfunction "~{CS}_39") (pintype "input"))
      (node (ref "IC11") (pin "7") (pinfunction "A6_7") (pintype "bidirectional"))
    )
  )
)
